# easy_bee_feather_route.net
KiCad netlist of a schematic drawn in EAGLE
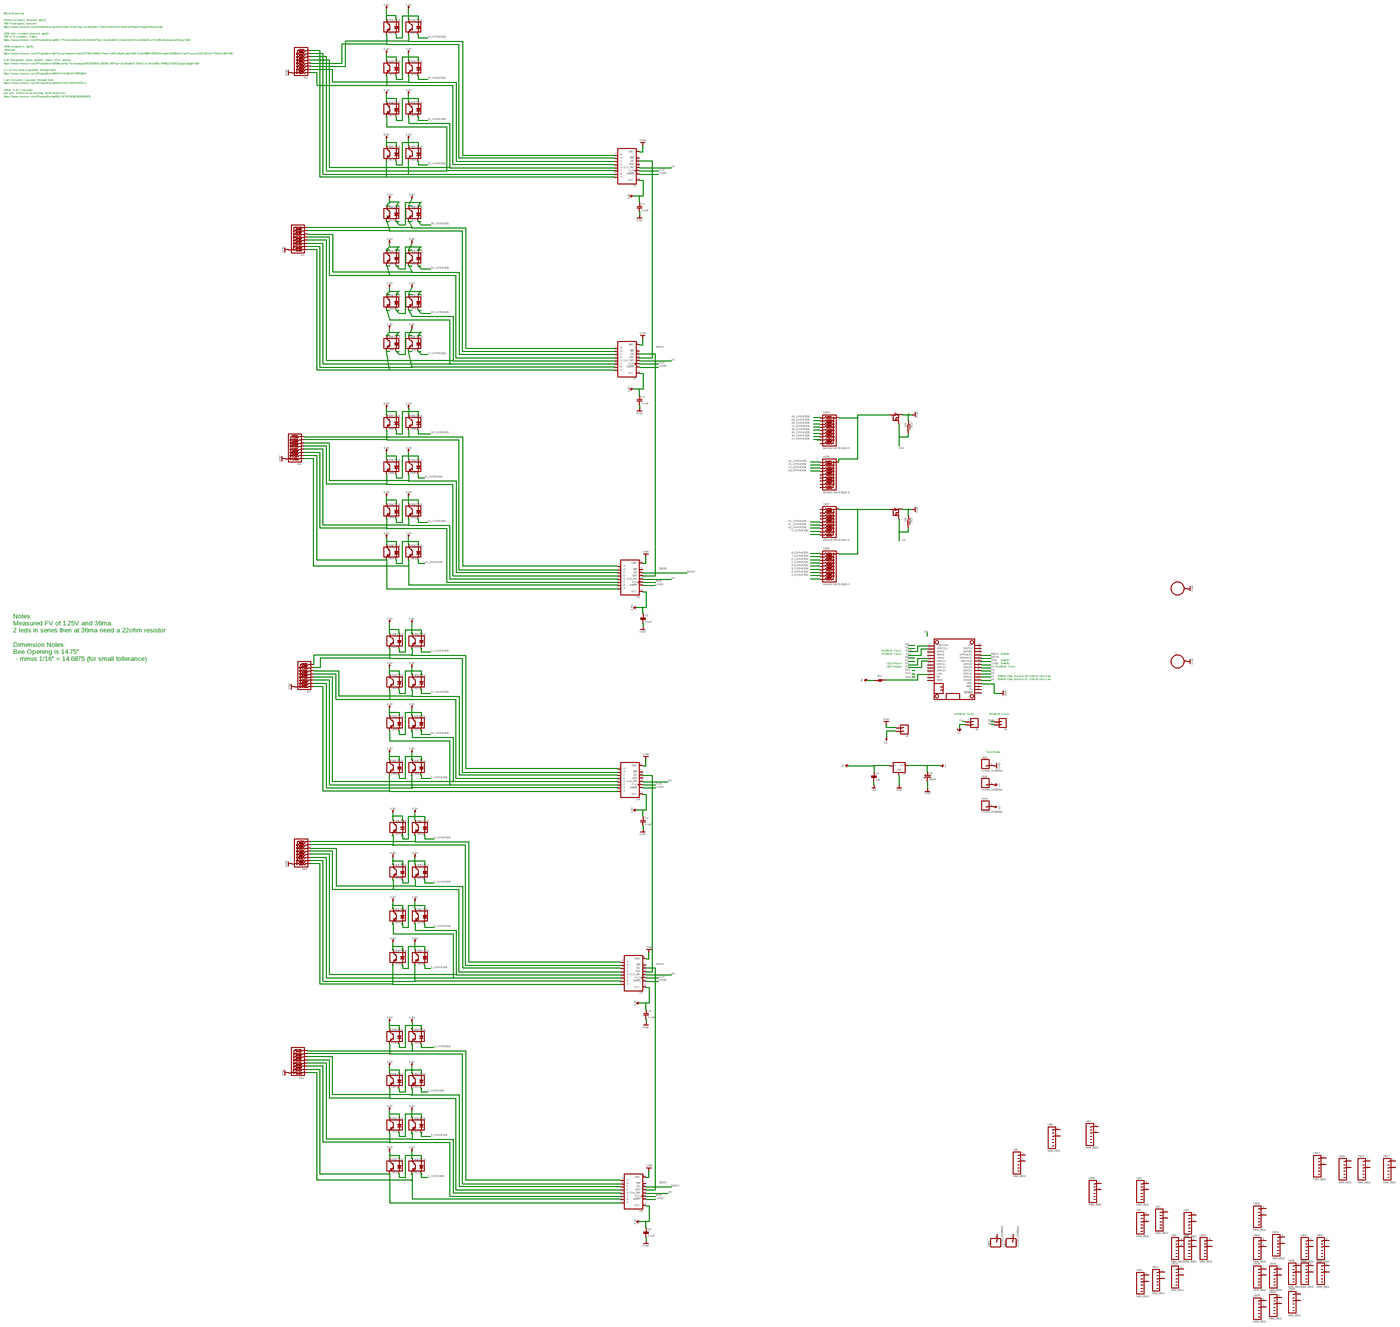
[diagram p0: schematic, sheet 1, overview]
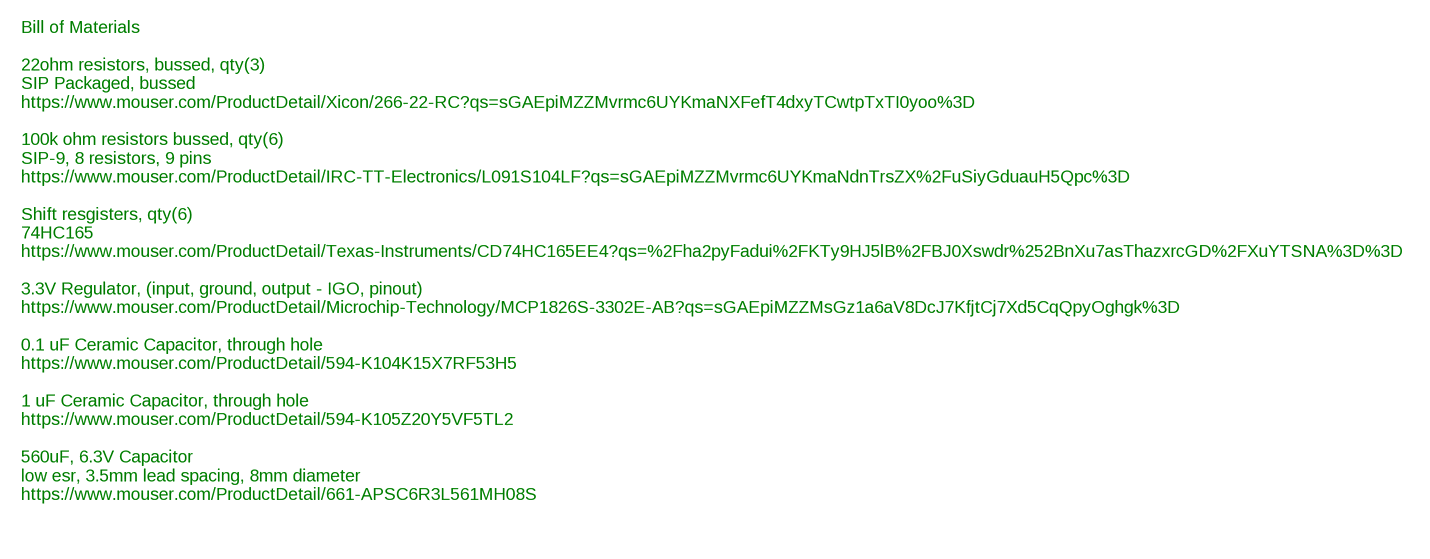
[diagram p1: schematic, sheet 1, part 1 of 5]
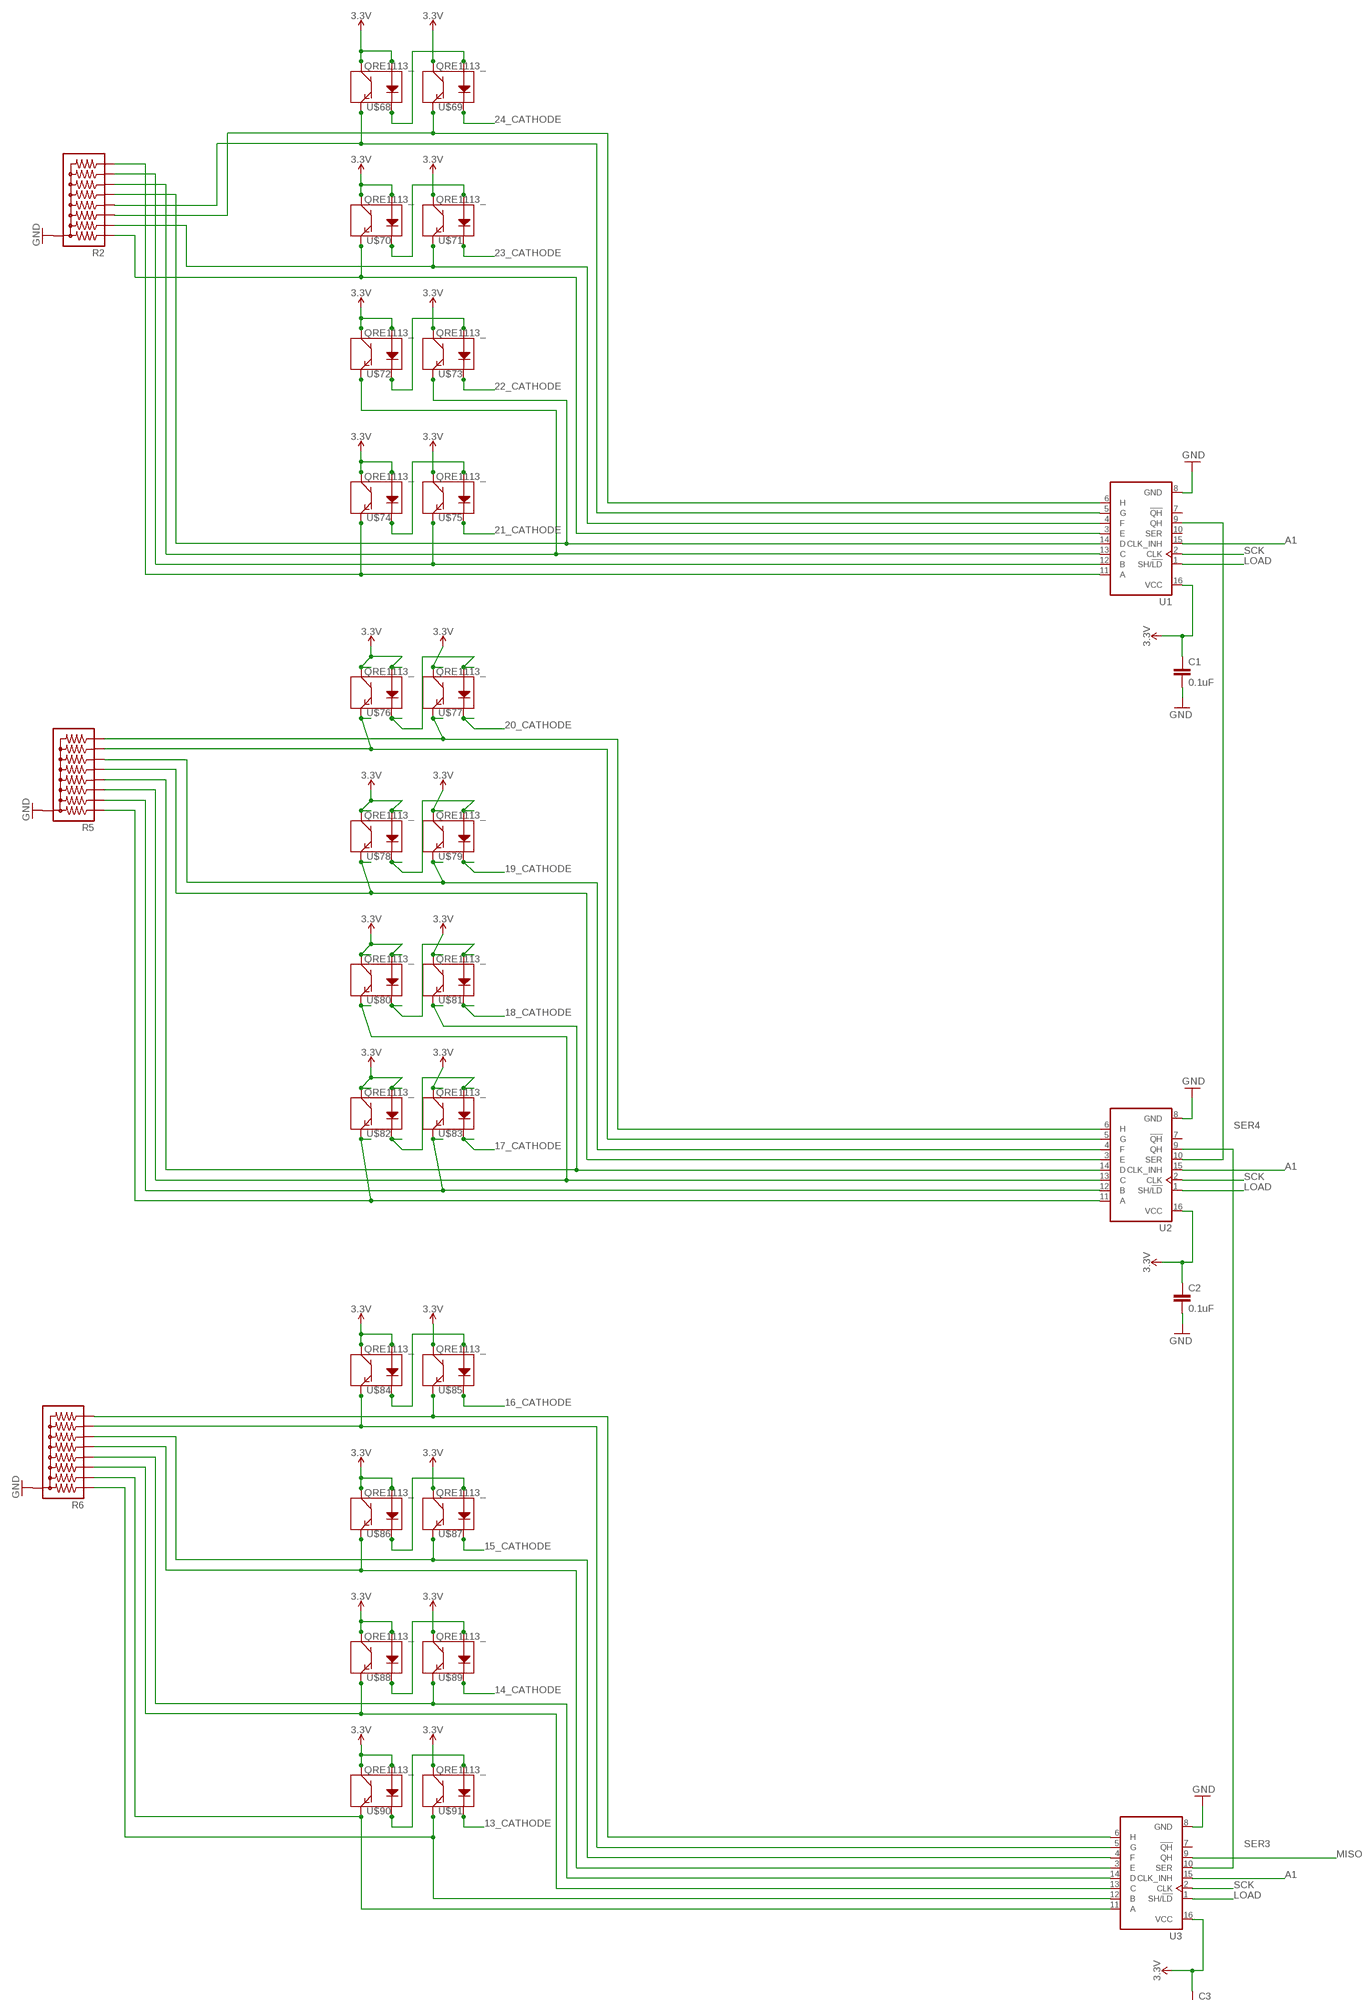
[diagram p2: schematic, sheet 1, part 2 of 5]
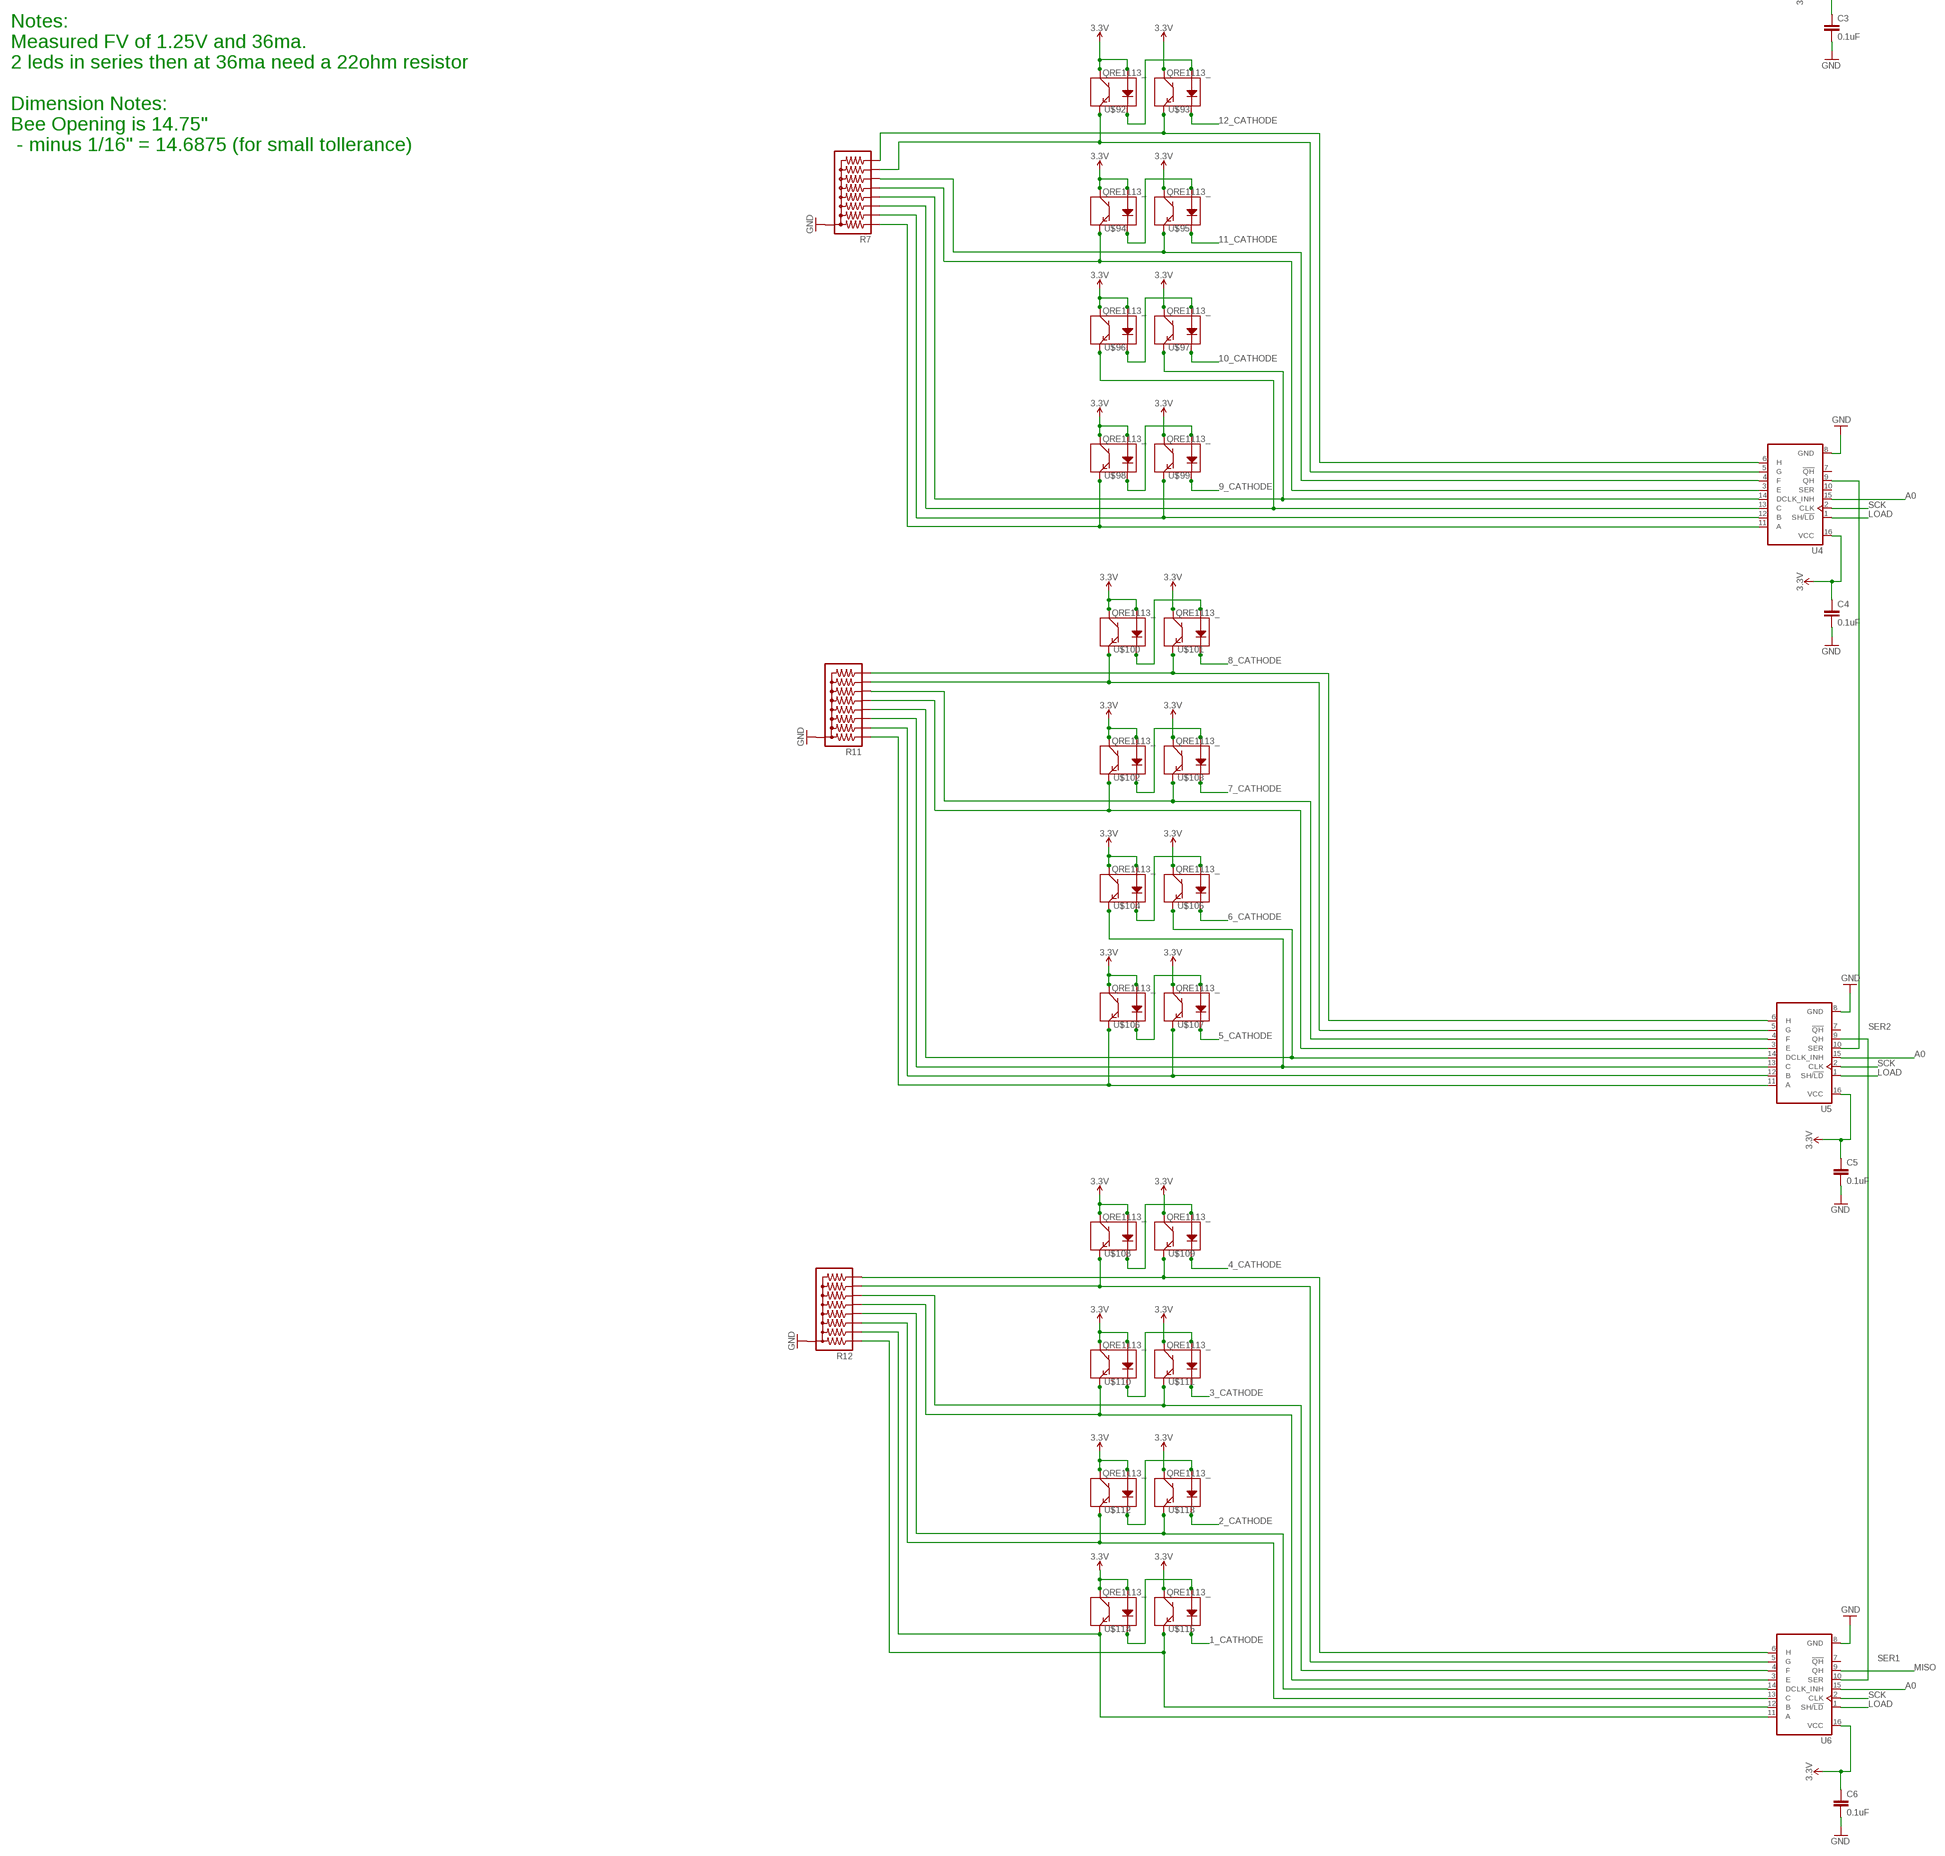
[diagram p3: schematic, sheet 1, part 3 of 5]
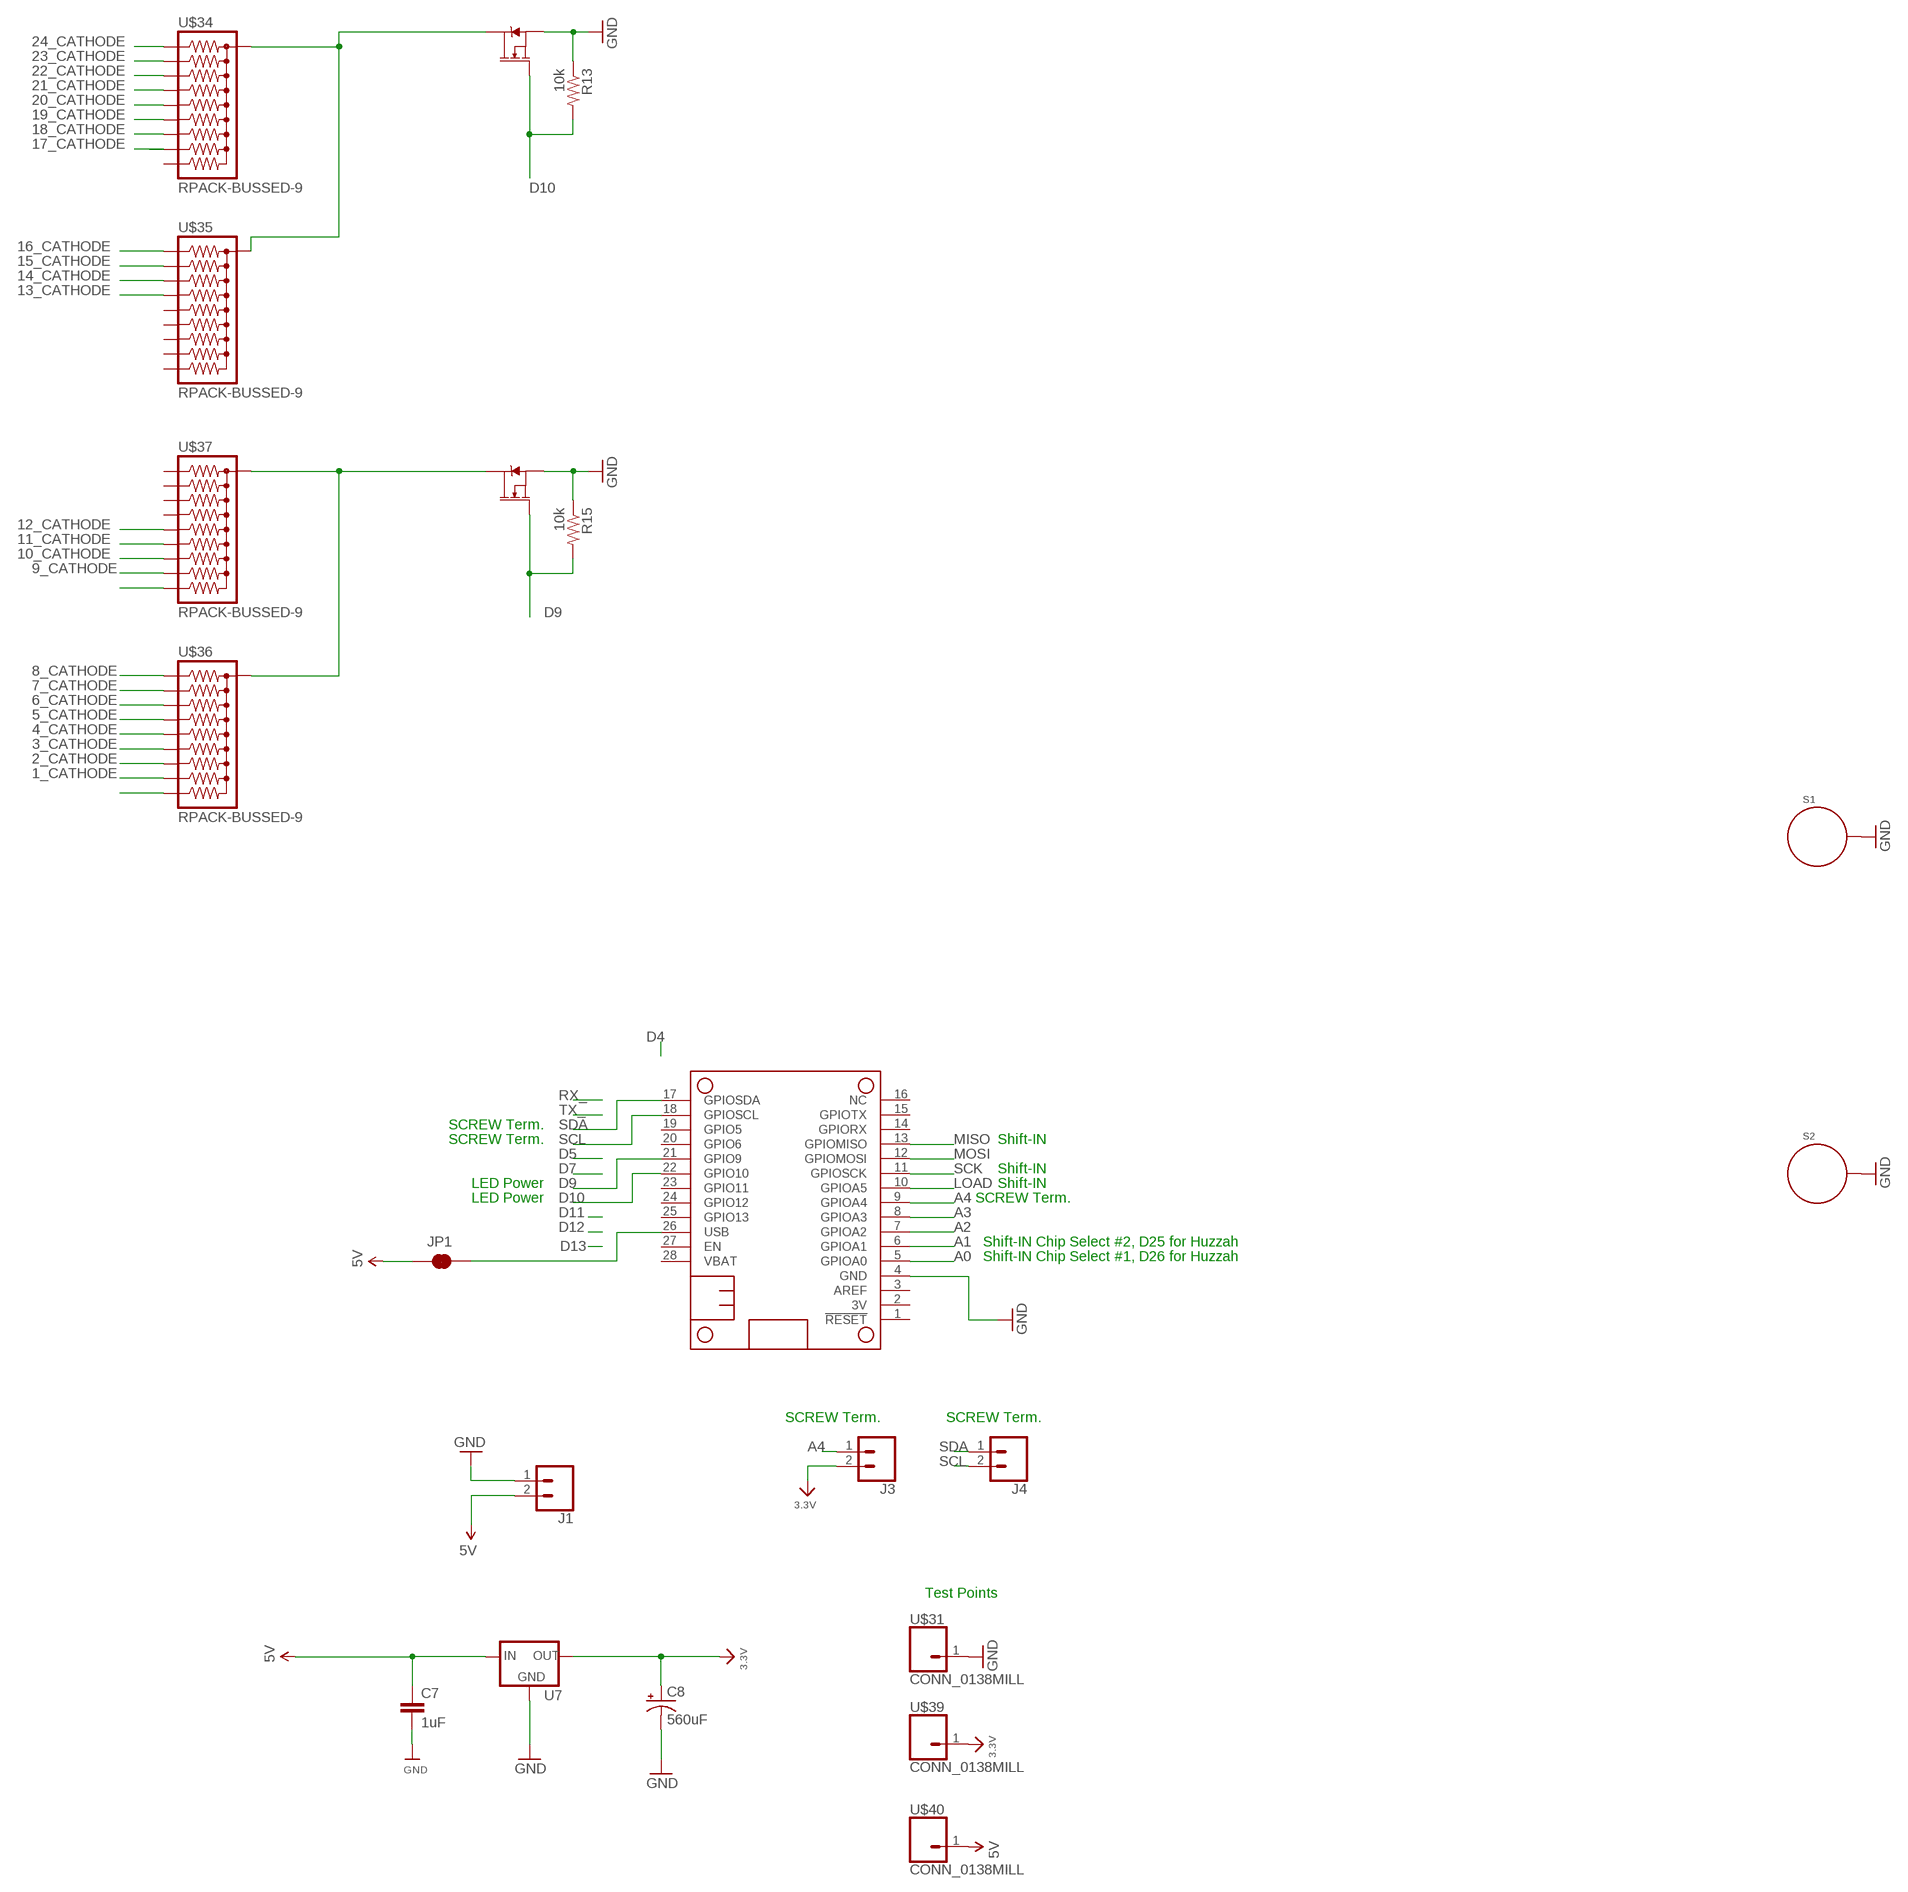
[diagram p4: schematic, sheet 1, part 4 of 5]
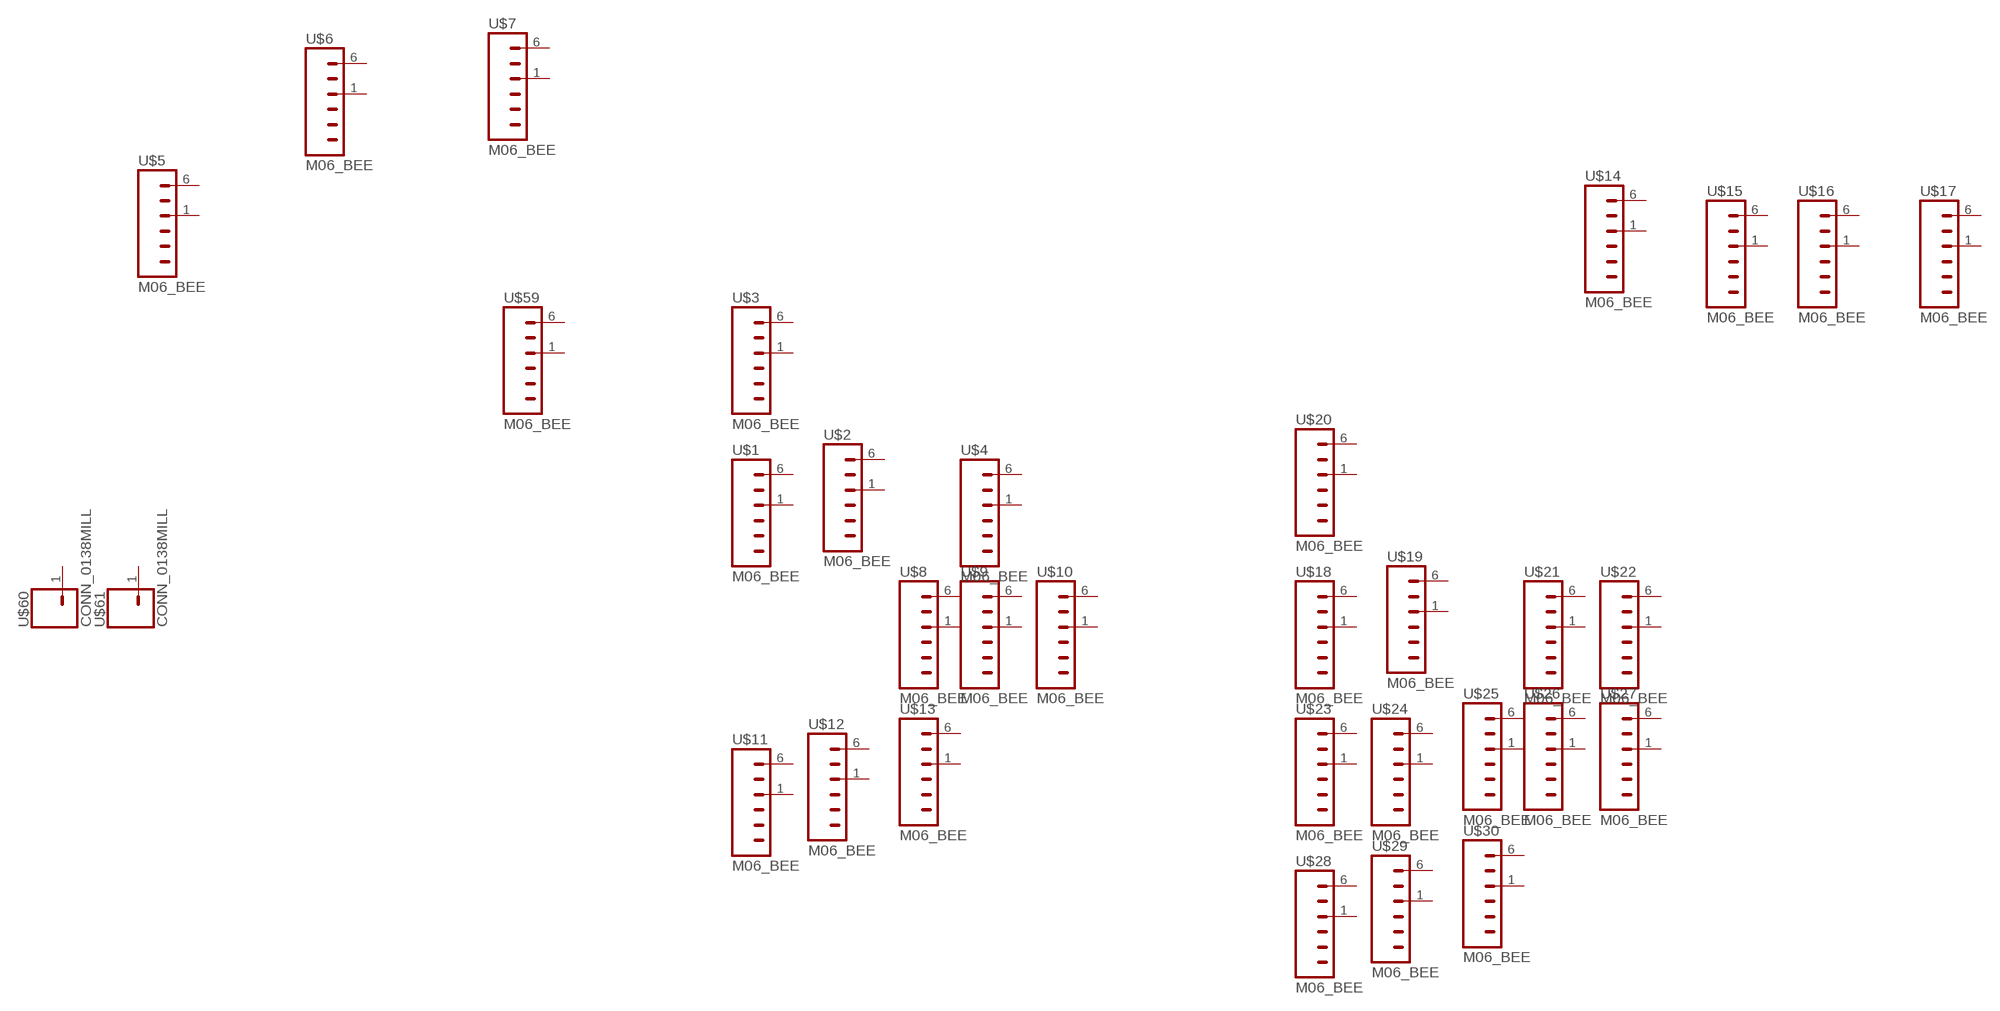
[diagram p5: schematic, sheet 1, part 5 of 5]

(export (version "E")
  (design (tool "Eeschema 10.0.6"))
  (components
    (comp (ref "C1")
      (value "0.1uF")
      (footprint "eagle-import:CAP-PTH-SMALL-KIT")
      (libsource (lib "eagle-import") (part "0.1UF-KIT-EZ-50V-20%"))
    )
    (comp (ref "C2")
      (value "0.1uF")
      (footprint "eagle-import:CAP-PTH-SMALL-KIT")
      (libsource (lib "eagle-import") (part "0.1UF-KIT-EZ-50V-20%"))
    )
    (comp (ref "C3")
      (value "0.1uF")
      (footprint "eagle-import:CAP-PTH-SMALL-KIT")
      (libsource (lib "eagle-import") (part "0.1UF-KIT-EZ-50V-20%"))
    )
    (comp (ref "C4")
      (value "0.1uF")
      (footprint "eagle-import:CAP-PTH-SMALL-KIT")
      (libsource (lib "eagle-import") (part "0.1UF-KIT-EZ-50V-20%"))
    )
    (comp (ref "C5")
      (value "0.1uF")
      (footprint "eagle-import:CAP-PTH-SMALL-KIT")
      (libsource (lib "eagle-import") (part "0.1UF-KIT-EZ-50V-20%"))
    )
    (comp (ref "C6")
      (value "0.1uF")
      (footprint "eagle-import:CAP-PTH-SMALL-KIT")
      (libsource (lib "eagle-import") (part "0.1UF-KIT-EZ-50V-20%"))
    )
    (comp (ref "C7")
      (value "1uF")
      (footprint "eagle-import:CAP-PTH-SMALL-KIT")
      (libsource (lib "eagle-import") (part "0.1UF-KIT-EZ-50V-20%"))
    )
    (comp (ref "C8")
      (value "560uF")
      (footprint "eagle-import:E3,5-8")
      (libsource (lib "eagle-import") (part "CPOL-USE3.5-8"))
    )
    (comp (ref "J1")
      (value "CONN_025MM")
      (footprint "eagle-import:SCREWTERMINAL-5MM-2")
      (libsource (lib "eagle-import") (part "CONN_025MM"))
    )
    (comp (ref "J3")
      (value "CONN_025MM")
      (footprint "eagle-import:SCREWTERMINAL-5MM-2")
      (libsource (lib "eagle-import") (part "CONN_025MM"))
    )
    (comp (ref "J4")
      (value "CONN_025MM")
      (footprint "eagle-import:SCREWTERMINAL-5MM-2")
      (libsource (lib "eagle-import") (part "CONN_025MM"))
    )
    (comp (ref "JP1")
      (value "JUMPER-SMT_2_NC_TRACE_SILK")
      (footprint "eagle-import:SMT-JUMPER_2_NC_TRACE_SILK")
      (libsource (lib "eagle-import") (part "JUMPER-SMT_2_NC_TRACE_SILK"))
    )
    (comp (ref "MS2")
      (value "FEATHERWING_NODIM")
      (footprint "eagle-import:FEATHERWING_DIM")
      (libsource (lib "eagle-import") (part "FEATHERWING_NODIM"))
    )
    (comp (ref "Q6")
      (value "60V/32A/35mΩ")
      (footprint "eagle-import:TO220V")
      (libsource (lib "eagle-import") (part "MOSFET-NCH-FQP30N06L"))
    )
    (comp (ref "Q7")
      (value "60V/32A/35mΩ")
      (footprint "eagle-import:TO220V")
      (libsource (lib "eagle-import") (part "MOSFET-NCH-FQP30N06L"))
    )
    (comp (ref "R2")
      (value "RPACK-BUSSED-8-SIP-PTH-8")
      (footprint "eagle-import:RPACK-SIP-PTH-8")
      (libsource (lib "eagle-import") (part "RPACK-BUSSED-8-SIP-PTH-8"))
    )
    (comp (ref "R5")
      (value "RPACK-BUSSED-8-SIP-PTH-8")
      (footprint "eagle-import:RPACK-SIP-PTH-8")
      (libsource (lib "eagle-import") (part "RPACK-BUSSED-8-SIP-PTH-8"))
    )
    (comp (ref "R6")
      (value "RPACK-BUSSED-8-SIP-PTH-8")
      (footprint "eagle-import:RPACK-SIP-PTH-8")
      (libsource (lib "eagle-import") (part "RPACK-BUSSED-8-SIP-PTH-8"))
    )
    (comp (ref "R7")
      (value "RPACK-BUSSED-8-SIP-PTH-8")
      (footprint "eagle-import:RPACK-SIP-PTH-8")
      (libsource (lib "eagle-import") (part "RPACK-BUSSED-8-SIP-PTH-8"))
    )
    (comp (ref "R11")
      (value "RPACK-BUSSED-8-SIP-PTH-8")
      (footprint "eagle-import:RPACK-SIP-PTH-8")
      (libsource (lib "eagle-import") (part "RPACK-BUSSED-8-SIP-PTH-8"))
    )
    (comp (ref "R12")
      (value "RPACK-BUSSED-8-SIP-PTH-8")
      (footprint "eagle-import:RPACK-SIP-PTH-8")
      (libsource (lib "eagle-import") (part "RPACK-BUSSED-8-SIP-PTH-8"))
    )
    (comp (ref "R13")
      (value "10k")
      (footprint "eagle-import:AXIAL-0.3")
      (libsource (lib "eagle-import") (part "RESISTORAXIAL-0.3"))
    )
    (comp (ref "R15")
      (value "10k")
      (footprint "eagle-import:AXIAL-0.3")
      (libsource (lib "eagle-import") (part "RESISTORAXIAL-0.3"))
    )
    (comp (ref "S1")
      (value "STANDOFF_ELECTRICAL5-32")
      (footprint "eagle-import:STANDOFF_ELECTRICAL_5_32")
      (libsource (lib "eagle-import") (part "STANDOFF_ELECTRICAL5-32"))
    )
    (comp (ref "S2")
      (value "STANDOFF_ELECTRICAL5-32")
      (footprint "eagle-import:STANDOFF_ELECTRICAL_5_32")
      (libsource (lib "eagle-import") (part "STANDOFF_ELECTRICAL5-32"))
    )
    (comp (ref "U$1")
      (value "M06_BEE")
      (footprint "eagle-import:1X06_BEE")
      (libsource (lib "eagle-import") (part "M06_BEE"))
    )
    (comp (ref "U$2")
      (value "M06_BEE")
      (footprint "eagle-import:1X06_BEE")
      (libsource (lib "eagle-import") (part "M06_BEE"))
    )
    (comp (ref "U$3")
      (value "M06_BEE")
      (footprint "eagle-import:1X06_BEE")
      (libsource (lib "eagle-import") (part "M06_BEE"))
    )
    (comp (ref "U$4")
      (value "M06_BEE")
      (footprint "eagle-import:1X06_BEE")
      (libsource (lib "eagle-import") (part "M06_BEE"))
    )
    (comp (ref "U$5")
      (value "M06_BEE")
      (footprint "eagle-import:1X06_BEE")
      (libsource (lib "eagle-import") (part "M06_BEE"))
    )
    (comp (ref "U$6")
      (value "M06_BEE")
      (footprint "eagle-import:1X06_BEE")
      (libsource (lib "eagle-import") (part "M06_BEE"))
    )
    (comp (ref "U$7")
      (value "M06_BEE")
      (footprint "eagle-import:1X06_BEE")
      (libsource (lib "eagle-import") (part "M06_BEE"))
    )
    (comp (ref "U$8")
      (value "M06_BEE")
      (footprint "eagle-import:1X06_BEE")
      (libsource (lib "eagle-import") (part "M06_BEE"))
    )
    (comp (ref "U$9")
      (value "M06_BEE")
      (footprint "eagle-import:1X06_BEE")
      (libsource (lib "eagle-import") (part "M06_BEE"))
    )
    (comp (ref "U$10")
      (value "M06_BEE")
      (footprint "eagle-import:1X06_BEE")
      (libsource (lib "eagle-import") (part "M06_BEE"))
    )
    (comp (ref "U$11")
      (value "M06_BEE")
      (footprint "eagle-import:1X06_BEE")
      (libsource (lib "eagle-import") (part "M06_BEE"))
    )
    (comp (ref "U$12")
      (value "M06_BEE")
      (footprint "eagle-import:1X06_BEE")
      (libsource (lib "eagle-import") (part "M06_BEE"))
    )
    (comp (ref "U$13")
      (value "M06_BEE")
      (footprint "eagle-import:1X06_BEE")
      (libsource (lib "eagle-import") (part "M06_BEE"))
    )
    (comp (ref "U$14")
      (value "M06_BEE")
      (footprint "eagle-import:1X06_BEE")
      (libsource (lib "eagle-import") (part "M06_BEE"))
    )
    (comp (ref "U$15")
      (value "M06_BEE")
      (footprint "eagle-import:1X06_BEE")
      (libsource (lib "eagle-import") (part "M06_BEE"))
    )
    (comp (ref "U$16")
      (value "M06_BEE")
      (footprint "eagle-import:1X06_BEE")
      (libsource (lib "eagle-import") (part "M06_BEE"))
    )
    (comp (ref "U$17")
      (value "M06_BEE")
      (footprint "eagle-import:1X06_BEE")
      (libsource (lib "eagle-import") (part "M06_BEE"))
    )
    (comp (ref "U$18")
      (value "M06_BEE")
      (footprint "eagle-import:1X06_BEE")
      (libsource (lib "eagle-import") (part "M06_BEE"))
    )
    (comp (ref "U$19")
      (value "M06_BEE")
      (footprint "eagle-import:1X06_BEE")
      (libsource (lib "eagle-import") (part "M06_BEE"))
    )
    (comp (ref "U$20")
      (value "M06_BEE")
      (footprint "eagle-import:1X06_BEE")
      (libsource (lib "eagle-import") (part "M06_BEE"))
    )
    (comp (ref "U$21")
      (value "M06_BEE")
      (footprint "eagle-import:1X06_BEE")
      (libsource (lib "eagle-import") (part "M06_BEE"))
    )
    (comp (ref "U$22")
      (value "M06_BEE")
      (footprint "eagle-import:1X06_BEE")
      (libsource (lib "eagle-import") (part "M06_BEE"))
    )
    (comp (ref "U$23")
      (value "M06_BEE")
      (footprint "eagle-import:1X06_BEE")
      (libsource (lib "eagle-import") (part "M06_BEE"))
    )
    (comp (ref "U$24")
      (value "M06_BEE")
      (footprint "eagle-import:1X06_BEE")
      (libsource (lib "eagle-import") (part "M06_BEE"))
    )
    (comp (ref "U$25")
      (value "M06_BEE")
      (footprint "eagle-import:1X06_BEE")
      (libsource (lib "eagle-import") (part "M06_BEE"))
    )
    (comp (ref "U$26")
      (value "M06_BEE")
      (footprint "eagle-import:1X06_BEE")
      (libsource (lib "eagle-import") (part "M06_BEE"))
    )
    (comp (ref "U$27")
      (value "M06_BEE")
      (footprint "eagle-import:1X06_BEE")
      (libsource (lib "eagle-import") (part "M06_BEE"))
    )
    (comp (ref "U$28")
      (value "M06_BEE")
      (footprint "eagle-import:1X06_BEE")
      (libsource (lib "eagle-import") (part "M06_BEE"))
    )
    (comp (ref "U$29")
      (value "M06_BEE")
      (footprint "eagle-import:1X06_BEE")
      (libsource (lib "eagle-import") (part "M06_BEE"))
    )
    (comp (ref "U$30")
      (value "M06_BEE")
      (footprint "eagle-import:1X06_BEE")
      (libsource (lib "eagle-import") (part "M06_BEE"))
    )
    (comp (ref "U$31")
      (value "CONN_0138MILL")
      (footprint "eagle-import:1X01-40MILL")
      (libsource (lib "eagle-import") (part "CONN_0138MILL"))
    )
    (comp (ref "U$34")
      (value "RPACK-BUSSED-9")
      (footprint "eagle-import:RPACK-SIP-PTH-9")
      (libsource (lib "eagle-import") (part "RPACK-BUSSED-9"))
    )
    (comp (ref "U$35")
      (value "RPACK-BUSSED-9")
      (footprint "eagle-import:RPACK-SIP-PTH-9")
      (libsource (lib "eagle-import") (part "RPACK-BUSSED-9"))
    )
    (comp (ref "U$36")
      (value "RPACK-BUSSED-9")
      (footprint "eagle-import:RPACK-SIP-PTH-9")
      (libsource (lib "eagle-import") (part "RPACK-BUSSED-9"))
    )
    (comp (ref "U$37")
      (value "RPACK-BUSSED-9")
      (footprint "eagle-import:RPACK-SIP-PTH-9")
      (libsource (lib "eagle-import") (part "RPACK-BUSSED-9"))
    )
    (comp (ref "U$39")
      (value "CONN_0138MILL")
      (footprint "eagle-import:1X01-40MILL")
      (libsource (lib "eagle-import") (part "CONN_0138MILL"))
    )
    (comp (ref "U$40")
      (value "CONN_0138MILL")
      (footprint "eagle-import:1X01-40MILL")
      (libsource (lib "eagle-import") (part "CONN_0138MILL"))
    )
    (comp (ref "U$59")
      (value "M06_BEE")
      (footprint "eagle-import:1X06_BEE")
      (libsource (lib "eagle-import") (part "M06_BEE"))
    )
    (comp (ref "U$60")
      (value "CONN_0138MILL")
      (footprint "eagle-import:1X01-40MILL")
      (libsource (lib "eagle-import") (part "CONN_0138MILL"))
    )
    (comp (ref "U$61")
      (value "CONN_0138MILL")
      (footprint "eagle-import:1X01-40MILL")
      (libsource (lib "eagle-import") (part "CONN_0138MILL"))
    )
    (comp (ref "U$68")
      (value "QRE1113_")
      (footprint "eagle-import:DIP400W50P180L360H200Q4")
      (libsource (lib "eagle-import") (part "QRE1113_"))
    )
    (comp (ref "U$69")
      (value "QRE1113_")
      (footprint "eagle-import:DIP400W50P180L360H200Q4")
      (libsource (lib "eagle-import") (part "QRE1113_"))
    )
    (comp (ref "U$70")
      (value "QRE1113_")
      (footprint "eagle-import:DIP400W50P180L360H200Q4")
      (libsource (lib "eagle-import") (part "QRE1113_"))
    )
    (comp (ref "U$71")
      (value "QRE1113_")
      (footprint "eagle-import:DIP400W50P180L360H200Q4")
      (libsource (lib "eagle-import") (part "QRE1113_"))
    )
    (comp (ref "U$72")
      (value "QRE1113_")
      (footprint "eagle-import:DIP400W50P180L360H200Q4")
      (libsource (lib "eagle-import") (part "QRE1113_"))
    )
    (comp (ref "U$73")
      (value "QRE1113_")
      (footprint "eagle-import:DIP400W50P180L360H200Q4")
      (libsource (lib "eagle-import") (part "QRE1113_"))
    )
    (comp (ref "U$74")
      (value "QRE1113_")
      (footprint "eagle-import:DIP400W50P180L360H200Q4")
      (libsource (lib "eagle-import") (part "QRE1113_"))
    )
    (comp (ref "U$75")
      (value "QRE1113_")
      (footprint "eagle-import:DIP400W50P180L360H200Q4")
      (libsource (lib "eagle-import") (part "QRE1113_"))
    )
    (comp (ref "U$76")
      (value "QRE1113_")
      (footprint "eagle-import:DIP400W50P180L360H200Q4")
      (libsource (lib "eagle-import") (part "QRE1113_"))
    )
    (comp (ref "U$77")
      (value "QRE1113_")
      (footprint "eagle-import:DIP400W50P180L360H200Q4")
      (libsource (lib "eagle-import") (part "QRE1113_"))
    )
    (comp (ref "U$78")
      (value "QRE1113_")
      (footprint "eagle-import:DIP400W50P180L360H200Q4")
      (libsource (lib "eagle-import") (part "QRE1113_"))
    )
    (comp (ref "U$79")
      (value "QRE1113_")
      (footprint "eagle-import:DIP400W50P180L360H200Q4")
      (libsource (lib "eagle-import") (part "QRE1113_"))
    )
    (comp (ref "U$80")
      (value "QRE1113_")
      (footprint "eagle-import:DIP400W50P180L360H200Q4")
      (libsource (lib "eagle-import") (part "QRE1113_"))
    )
    (comp (ref "U$81")
      (value "QRE1113_")
      (footprint "eagle-import:DIP400W50P180L360H200Q4")
      (libsource (lib "eagle-import") (part "QRE1113_"))
    )
    (comp (ref "U$82")
      (value "QRE1113_")
      (footprint "eagle-import:DIP400W50P180L360H200Q4")
      (libsource (lib "eagle-import") (part "QRE1113_"))
    )
    (comp (ref "U$83")
      (value "QRE1113_")
      (footprint "eagle-import:DIP400W50P180L360H200Q4")
      (libsource (lib "eagle-import") (part "QRE1113_"))
    )
    (comp (ref "U$84")
      (value "QRE1113_")
      (footprint "eagle-import:DIP400W50P180L360H200Q4")
      (libsource (lib "eagle-import") (part "QRE1113_"))
    )
    (comp (ref "U$85")
      (value "QRE1113_")
      (footprint "eagle-import:DIP400W50P180L360H200Q4")
      (libsource (lib "eagle-import") (part "QRE1113_"))
    )
    (comp (ref "U$86")
      (value "QRE1113_")
      (footprint "eagle-import:DIP400W50P180L360H200Q4")
      (libsource (lib "eagle-import") (part "QRE1113_"))
    )
    (comp (ref "U$87")
      (value "QRE1113_")
      (footprint "eagle-import:DIP400W50P180L360H200Q4")
      (libsource (lib "eagle-import") (part "QRE1113_"))
    )
    (comp (ref "U$88")
      (value "QRE1113_")
      (footprint "eagle-import:DIP400W50P180L360H200Q4")
      (libsource (lib "eagle-import") (part "QRE1113_"))
    )
    (comp (ref "U$89")
      (value "QRE1113_")
      (footprint "eagle-import:DIP400W50P180L360H200Q4")
      (libsource (lib "eagle-import") (part "QRE1113_"))
    )
    (comp (ref "U$90")
      (value "QRE1113_")
      (footprint "eagle-import:DIP400W50P180L360H200Q4")
      (libsource (lib "eagle-import") (part "QRE1113_"))
    )
    (comp (ref "U$91")
      (value "QRE1113_")
      (footprint "eagle-import:DIP400W50P180L360H200Q4")
      (libsource (lib "eagle-import") (part "QRE1113_"))
    )
    (comp (ref "U$92")
      (value "QRE1113_")
      (footprint "eagle-import:DIP400W50P180L360H200Q4")
      (libsource (lib "eagle-import") (part "QRE1113_"))
    )
    (comp (ref "U$93")
      (value "QRE1113_")
      (footprint "eagle-import:DIP400W50P180L360H200Q4")
      (libsource (lib "eagle-import") (part "QRE1113_"))
    )
    (comp (ref "U$94")
      (value "QRE1113_")
      (footprint "eagle-import:DIP400W50P180L360H200Q4")
      (libsource (lib "eagle-import") (part "QRE1113_"))
    )
    (comp (ref "U$95")
      (value "QRE1113_")
      (footprint "eagle-import:DIP400W50P180L360H200Q4")
      (libsource (lib "eagle-import") (part "QRE1113_"))
    )
    (comp (ref "U$96")
      (value "QRE1113_")
      (footprint "eagle-import:DIP400W50P180L360H200Q4")
      (libsource (lib "eagle-import") (part "QRE1113_"))
    )
    (comp (ref "U$97")
      (value "QRE1113_")
      (footprint "eagle-import:DIP400W50P180L360H200Q4")
      (libsource (lib "eagle-import") (part "QRE1113_"))
    )
    (comp (ref "U$98")
      (value "QRE1113_")
      (footprint "eagle-import:DIP400W50P180L360H200Q4")
      (libsource (lib "eagle-import") (part "QRE1113_"))
    )
    (comp (ref "U$99")
      (value "QRE1113_")
      (footprint "eagle-import:DIP400W50P180L360H200Q4")
      (libsource (lib "eagle-import") (part "QRE1113_"))
    )
    (comp (ref "U$100")
      (value "QRE1113_")
      (footprint "eagle-import:DIP400W50P180L360H200Q4")
      (libsource (lib "eagle-import") (part "QRE1113_"))
    )
    (comp (ref "U$101")
      (value "QRE1113_")
      (footprint "eagle-import:DIP400W50P180L360H200Q4")
      (libsource (lib "eagle-import") (part "QRE1113_"))
    )
    (comp (ref "U$102")
      (value "QRE1113_")
      (footprint "eagle-import:DIP400W50P180L360H200Q4")
      (libsource (lib "eagle-import") (part "QRE1113_"))
    )
    (comp (ref "U$103")
      (value "QRE1113_")
      (footprint "eagle-import:DIP400W50P180L360H200Q4")
      (libsource (lib "eagle-import") (part "QRE1113_"))
    )
    (comp (ref "U$104")
      (value "QRE1113_")
      (footprint "eagle-import:DIP400W50P180L360H200Q4")
      (libsource (lib "eagle-import") (part "QRE1113_"))
    )
    (comp (ref "U$105")
      (value "QRE1113_")
      (footprint "eagle-import:DIP400W50P180L360H200Q4")
      (libsource (lib "eagle-import") (part "QRE1113_"))
    )
    (comp (ref "U$106")
      (value "QRE1113_")
      (footprint "eagle-import:DIP400W50P180L360H200Q4")
      (libsource (lib "eagle-import") (part "QRE1113_"))
    )
    (comp (ref "U$107")
      (value "QRE1113_")
      (footprint "eagle-import:DIP400W50P180L360H200Q4")
      (libsource (lib "eagle-import") (part "QRE1113_"))
    )
    (comp (ref "U$108")
      (value "QRE1113_")
      (footprint "eagle-import:DIP400W50P180L360H200Q4")
      (libsource (lib "eagle-import") (part "QRE1113_"))
    )
    (comp (ref "U$109")
      (value "QRE1113_")
      (footprint "eagle-import:DIP400W50P180L360H200Q4")
      (libsource (lib "eagle-import") (part "QRE1113_"))
    )
    (comp (ref "U$110")
      (value "QRE1113_")
      (footprint "eagle-import:DIP400W50P180L360H200Q4")
      (libsource (lib "eagle-import") (part "QRE1113_"))
    )
    (comp (ref "U$111")
      (value "QRE1113_")
      (footprint "eagle-import:DIP400W50P180L360H200Q4")
      (libsource (lib "eagle-import") (part "QRE1113_"))
    )
    (comp (ref "U$112")
      (value "QRE1113_")
      (footprint "eagle-import:DIP400W50P180L360H200Q4")
      (libsource (lib "eagle-import") (part "QRE1113_"))
    )
    (comp (ref "U$113")
      (value "QRE1113_")
      (footprint "eagle-import:DIP400W50P180L360H200Q4")
      (libsource (lib "eagle-import") (part "QRE1113_"))
    )
    (comp (ref "U$114")
      (value "QRE1113_")
      (footprint "eagle-import:DIP400W50P180L360H200Q4")
      (libsource (lib "eagle-import") (part "QRE1113_"))
    )
    (comp (ref "U$115")
      (value "QRE1113_")
      (footprint "eagle-import:DIP400W50P180L360H200Q4")
      (libsource (lib "eagle-import") (part "QRE1113_"))
    )
    (comp (ref "U1")
      (value "74165")
      (footprint "eagle-import:DIP16")
      (libsource (lib "eagle-import") (part "74165"))
    )
    (comp (ref "U2")
      (value "74165")
      (footprint "eagle-import:DIP16")
      (libsource (lib "eagle-import") (part "74165"))
    )
    (comp (ref "U3")
      (value "74165")
      (footprint "eagle-import:DIP16")
      (libsource (lib "eagle-import") (part "74165"))
    )
    (comp (ref "U4")
      (value "74165")
      (footprint "eagle-import:DIP16")
      (libsource (lib "eagle-import") (part "74165"))
    )
    (comp (ref "U5")
      (value "74165")
      (footprint "eagle-import:DIP16")
      (libsource (lib "eagle-import") (part "74165"))
    )
    (comp (ref "U6")
      (value "74165")
      (footprint "eagle-import:DIP16")
      (libsource (lib "eagle-import") (part "74165"))
    )
    (comp (ref "U7")
      (value "V_REG_78XXSINK")
      (footprint "eagle-import:TO220-IGO")
      (libsource (lib "eagle-import") (part "V_REG_78XXSINK"))
    )
  )
  (nets
    (net (code "1") (name "/1_CATHODE") (class "Default")
      (node (ref "U$115") (pin "2") (pinfunction "K_2") (pintype "bidirectional"))
      (node (ref "U$36") (pin "P$9") (pinfunction "9_P$9") (pintype "passive"))
    )
    (net (code "2") (name "/2_CATHODE") (class "Default")
      (node (ref "U$113") (pin "2") (pinfunction "K_2") (pintype "bidirectional"))
      (node (ref "U$36") (pin "P$8") (pinfunction "8_P$8") (pintype "passive"))
    )
    (net (code "3") (name "/3V") (class "Default")
      (node (ref "MS2") (pin "2") (pinfunction "3V_2") (pintype "power_in"))
    )
    (net (code "4") (name "/3_CATHODE") (class "Default")
      (node (ref "U$111") (pin "2") (pinfunction "K_2") (pintype "bidirectional"))
      (node (ref "U$36") (pin "P$7") (pinfunction "7_P$7") (pintype "passive"))
    )
    (net (code "5") (name "/4_CATHODE") (class "Default")
      (node (ref "U$109") (pin "2") (pinfunction "K_2") (pintype "bidirectional"))
      (node (ref "U$36") (pin "P$6") (pinfunction "6_P$6") (pintype "passive"))
    )
    (net (code "6") (name "/5_CATHODE") (class "Default")
      (node (ref "U$107") (pin "2") (pinfunction "K_2") (pintype "bidirectional"))
      (node (ref "U$36") (pin "P$5") (pinfunction "5_P$5") (pintype "passive"))
    )
    (net (code "7") (name "/6_CATHODE") (class "Default")
      (node (ref "U$105") (pin "2") (pinfunction "K_2") (pintype "bidirectional"))
      (node (ref "U$36") (pin "P$4") (pinfunction "4_P$4") (pintype "passive"))
    )
    (net (code "8") (name "/7_CATHODE") (class "Default")
      (node (ref "U$103") (pin "2") (pinfunction "K_2") (pintype "bidirectional"))
      (node (ref "U$36") (pin "P$3") (pinfunction "3_P$3") (pintype "passive"))
    )
    (net (code "9") (name "/8_CATHODE") (class "Default")
      (node (ref "U$101") (pin "2") (pinfunction "K_2") (pintype "bidirectional"))
      (node (ref "U$36") (pin "P$2") (pinfunction "2_P$2") (pintype "passive"))
    )
    (net (code "10") (name "/9_CATHODE") (class "Default")
      (node (ref "U$37") (pin "P$9") (pinfunction "9_P$9") (pintype "passive"))
      (node (ref "U$99") (pin "2") (pinfunction "K_2") (pintype "bidirectional"))
    )
    (net (code "11") (name "/10_CATHODE") (class "Default")
      (node (ref "U$37") (pin "P$8") (pinfunction "8_P$8") (pintype "passive"))
      (node (ref "U$97") (pin "2") (pinfunction "K_2") (pintype "bidirectional"))
    )
    (net (code "12") (name "/11_CATHODE") (class "Default")
      (node (ref "U$37") (pin "P$7") (pinfunction "7_P$7") (pintype "passive"))
      (node (ref "U$95") (pin "2") (pinfunction "K_2") (pintype "bidirectional"))
    )
    (net (code "13") (name "/12_CATHODE") (class "Default")
      (node (ref "U$37") (pin "P$6") (pinfunction "6_P$6") (pintype "passive"))
      (node (ref "U$93") (pin "2") (pinfunction "K_2") (pintype "bidirectional"))
    )
    (net (code "14") (name "/13_CATHODE") (class "Default")
      (node (ref "U$35") (pin "P$5") (pinfunction "5_P$5") (pintype "passive"))
      (node (ref "U$91") (pin "2") (pinfunction "K_2") (pintype "bidirectional"))
    )
    (net (code "15") (name "/14_CATHODE") (class "Default")
      (node (ref "U$35") (pin "P$4") (pinfunction "4_P$4") (pintype "passive"))
      (node (ref "U$89") (pin "2") (pinfunction "K_2") (pintype "bidirectional"))
    )
    (net (code "16") (name "/15_CATHODE") (class "Default")
      (node (ref "U$35") (pin "P$3") (pinfunction "3_P$3") (pintype "passive"))
      (node (ref "U$87") (pin "2") (pinfunction "K_2") (pintype "bidirectional"))
    )
    (net (code "17") (name "/16_CATHODE") (class "Default")
      (node (ref "U$35") (pin "P$2") (pinfunction "2_P$2") (pintype "passive"))
      (node (ref "U$85") (pin "2") (pinfunction "K_2") (pintype "bidirectional"))
    )
    (net (code "18") (name "/17_CATHODE") (class "Default")
      (node (ref "U$34") (pin "P$9") (pinfunction "9_P$9") (pintype "passive"))
      (node (ref "U$83") (pin "2") (pinfunction "K_2") (pintype "bidirectional"))
    )
    (net (code "19") (name "/18_CATHODE") (class "Default")
      (node (ref "U$34") (pin "P$8") (pinfunction "8_P$8") (pintype "passive"))
      (node (ref "U$81") (pin "2") (pinfunction "K_2") (pintype "bidirectional"))
    )
    (net (code "20") (name "/19_CATHODE") (class "Default")
      (node (ref "U$34") (pin "P$7") (pinfunction "7_P$7") (pintype "passive"))
      (node (ref "U$79") (pin "2") (pinfunction "K_2") (pintype "bidirectional"))
    )
    (net (code "21") (name "/20_CATHODE") (class "Default")
      (node (ref "U$34") (pin "P$6") (pinfunction "6_P$6") (pintype "passive"))
      (node (ref "U$77") (pin "2") (pinfunction "K_2") (pintype "bidirectional"))
    )
    (net (code "22") (name "/21_CATHODE") (class "Default")
      (node (ref "U$34") (pin "P$5") (pinfunction "5_P$5") (pintype "passive"))
      (node (ref "U$75") (pin "2") (pinfunction "K_2") (pintype "bidirectional"))
    )
    (net (code "23") (name "/22_CATHODE") (class "Default")
      (node (ref "U$34") (pin "P$4") (pinfunction "4_P$4") (pintype "passive"))
      (node (ref "U$73") (pin "2") (pinfunction "K_2") (pintype "bidirectional"))
    )
    (net (code "24") (name "/23_CATHODE") (class "Default")
      (node (ref "U$34") (pin "P$3") (pinfunction "3_P$3") (pintype "passive"))
      (node (ref "U$71") (pin "2") (pinfunction "K_2") (pintype "bidirectional"))
    )
    (net (code "25") (name "/24_CATHODE") (class "Default")
      (node (ref "U$34") (pin "P$2") (pinfunction "2_P$2") (pintype "passive"))
      (node (ref "U$69") (pin "2") (pinfunction "K_2") (pintype "bidirectional"))
    )
    (net (code "26") (name "/A0") (class "Default")
      (node (ref "MS2") (pin "5") (pinfunction "GPIOA0_5") (pintype "bidirectional"))
      (node (ref "U4") (pin "15") (pinfunction "CLK_INH_15") (pintype "input"))
      (node (ref "U5") (pin "15") (pinfunction "CLK_INH_15") (pintype "input"))
      (node (ref "U6") (pin "15") (pinfunction "CLK_INH_15") (pintype "input"))
    )
    (net (code "27") (name "/A1") (class "Default")
      (node (ref "MS2") (pin "6") (pinfunction "GPIOA1_6") (pintype "bidirectional"))
      (node (ref "U1") (pin "15") (pinfunction "CLK_INH_15") (pintype "input"))
      (node (ref "U2") (pin "15") (pinfunction "CLK_INH_15") (pintype "input"))
      (node (ref "U3") (pin "15") (pinfunction "CLK_INH_15") (pintype "input"))
    )
    (net (code "28") (name "/A2") (class "Default")
      (node (ref "MS2") (pin "7") (pinfunction "GPIOA2_7") (pintype "bidirectional"))
    )
    (net (code "29") (name "/A3") (class "Default")
      (node (ref "MS2") (pin "8") (pinfunction "GPIOA3_8") (pintype "bidirectional"))
    )
    (net (code "30") (name "/A4") (class "Default")
      (node (ref "J3") (pin "1") (pinfunction "1_1") (pintype "passive"))
      (node (ref "MS2") (pin "9") (pinfunction "GPIOA4_9") (pintype "bidirectional"))
    )
    (net (code "34") (name "/D9") (class "Default")
      (node (ref "MS2") (pin "21") (pinfunction "GPIO9_21") (pintype "bidirectional"))
      (node (ref "Q7") (pin "1") (pinfunction "G_1") (pintype "bidirectional"))
      (node (ref "R15") (pin "P$2") (pinfunction "2_P$2") (pintype "passive"))
    )
    (net (code "35") (name "/D10") (class "Default")
      (node (ref "MS2") (pin "22") (pinfunction "GPIO10_22") (pintype "bidirectional"))
      (node (ref "Q6") (pin "1") (pinfunction "G_1") (pintype "bidirectional"))
      (node (ref "R13") (pin "P$2") (pinfunction "2_P$2") (pintype "passive"))
    )
    (net (code "39") (name "/LOAD") (class "Default")
      (node (ref "MS2") (pin "10") (pinfunction "GPIOA5_10") (pintype "bidirectional"))
      (node (ref "U1") (pin "1") (pinfunction "SH/~{LD}_1") (pintype "input"))
      (node (ref "U2") (pin "1") (pinfunction "SH/~{LD}_1") (pintype "input"))
      (node (ref "U3") (pin "1") (pinfunction "SH/~{LD}_1") (pintype "input"))
      (node (ref "U4") (pin "1") (pinfunction "SH/~{LD}_1") (pintype "input"))
      (node (ref "U5") (pin "1") (pinfunction "SH/~{LD}_1") (pintype "input"))
      (node (ref "U6") (pin "1") (pinfunction "SH/~{LD}_1") (pintype "input"))
    )
    (net (code "40") (name "/MISO") (class "Default")
      (node (ref "MS2") (pin "13") (pinfunction "GPIOMISO_13") (pintype "bidirectional"))
      (node (ref "U3") (pin "9") (pinfunction "QH_9") (pintype "tri_state"))
      (node (ref "U6") (pin "9") (pinfunction "QH_9") (pintype "tri_state"))
    )
    (net (code "41") (name "/MOSI") (class "Default")
      (node (ref "MS2") (pin "12") (pinfunction "GPIOMOSI_12") (pintype "bidirectional"))
    )
    (net (code "43") (name "/SCK") (class "Default")
      (node (ref "MS2") (pin "11") (pinfunction "GPIOSCK_11") (pintype "bidirectional"))
      (node (ref "U1") (pin "2") (pinfunction "CLK_2") (pintype "input"))
      (node (ref "U2") (pin "2") (pinfunction "CLK_2") (pintype "input"))
      (node (ref "U3") (pin "2") (pinfunction "CLK_2") (pintype "input"))
      (node (ref "U4") (pin "2") (pinfunction "CLK_2") (pintype "input"))
      (node (ref "U5") (pin "2") (pinfunction "CLK_2") (pintype "input"))
      (node (ref "U6") (pin "2") (pinfunction "CLK_2") (pintype "input"))
    )
    (net (code "44") (name "/SCL") (class "Default")
      (node (ref "J4") (pin "2") (pinfunction "2_2") (pintype "passive"))
      (node (ref "MS2") (pin "18") (pinfunction "GPIOSCL_18") (pintype "bidirectional"))
    )
    (net (code "45") (name "/SDA") (class "Default")
      (node (ref "J4") (pin "1") (pinfunction "1_1") (pintype "passive"))
      (node (ref "MS2") (pin "17") (pinfunction "GPIOSDA_17") (pintype "bidirectional"))
    )
    (net (code "46") (name "/SER1") (class "Default")
      (node (ref "U5") (pin "9") (pinfunction "QH_9") (pintype "tri_state"))
      (node (ref "U6") (pin "10") (pinfunction "SER_10") (pintype "input"))
    )
    (net (code "47") (name "/SER2") (class "Default")
      (node (ref "U4") (pin "9") (pinfunction "QH_9") (pintype "tri_state"))
      (node (ref "U5") (pin "10") (pinfunction "SER_10") (pintype "input"))
    )
    (net (code "48") (name "/SER3") (class "Default")
      (node (ref "U2") (pin "9") (pinfunction "QH_9") (pintype "tri_state"))
      (node (ref "U3") (pin "10") (pinfunction "SER_10") (pintype "input"))
    )
    (net (code "49") (name "/SER4") (class "Default")
      (node (ref "U1") (pin "9") (pinfunction "QH_9") (pintype "tri_state"))
      (node (ref "U2") (pin "10") (pinfunction "SER_10") (pintype "input"))
    )
    (net (code "51") (name "/VBAT") (class "Default")
      (node (ref "MS2") (pin "28") (pinfunction "VBAT_28") (pintype "power_in"))
    )
    (net (code "52") (name "3.3V") (class "Default")
      (node (ref "C1") (pin "1") (pinfunction "1_1") (pintype "passive"))
      (node (ref "C2") (pin "1") (pinfunction "1_1") (pintype "passive"))
      (node (ref "C3") (pin "1") (pinfunction "1_1") (pintype "passive"))
      (node (ref "C4") (pin "1") (pinfunction "1_1") (pintype "passive"))
      (node (ref "C5") (pin "1") (pinfunction "1_1") (pintype "passive"))
      (node (ref "C6") (pin "1") (pinfunction "1_1") (pintype "passive"))
      (node (ref "C8") (pin "+") (pinfunction "+_+") (pintype "passive"))
      (node (ref "J3") (pin "2") (pinfunction "2_2") (pintype "passive"))
      (node (ref "U$100") (pin "1") (pinfunction "A_1") (pintype "bidirectional"))
      (node (ref "U$100") (pin "3") (pinfunction "C_3") (pintype "bidirectional"))
      (node (ref "U$101") (pin "3") (pinfunction "C_3") (pintype "bidirectional"))
      (node (ref "U$102") (pin "1") (pinfunction "A_1") (pintype "bidirectional"))
      (node (ref "U$102") (pin "3") (pinfunction "C_3") (pintype "bidirectional"))
      (node (ref "U$103") (pin "3") (pinfunction "C_3") (pintype "bidirectional"))
      (node (ref "U$104") (pin "1") (pinfunction "A_1") (pintype "bidirectional"))
      (node (ref "U$104") (pin "3") (pinfunction "C_3") (pintype "bidirectional"))
      (node (ref "U$105") (pin "3") (pinfunction "C_3") (pintype "bidirectional"))
      (node (ref "U$106") (pin "1") (pinfunction "A_1") (pintype "bidirectional"))
      (node (ref "U$106") (pin "3") (pinfunction "C_3") (pintype "bidirectional"))
      (node (ref "U$107") (pin "3") (pinfunction "C_3") (pintype "bidirectional"))
      (node (ref "U$108") (pin "1") (pinfunction "A_1") (pintype "bidirectional"))
      (node (ref "U$108") (pin "3") (pinfunction "C_3") (pintype "bidirectional"))
      (node (ref "U$109") (pin "3") (pinfunction "C_3") (pintype "bidirectional"))
      (node (ref "U$110") (pin "1") (pinfunction "A_1") (pintype "bidirectional"))
      (node (ref "U$110") (pin "3") (pinfunction "C_3") (pintype "bidirectional"))
      (node (ref "U$111") (pin "3") (pinfunction "C_3") (pintype "bidirectional"))
      (node (ref "U$112") (pin "1") (pinfunction "A_1") (pintype "bidirectional"))
      (node (ref "U$112") (pin "3") (pinfunction "C_3") (pintype "bidirectional"))
      (node (ref "U$113") (pin "3") (pinfunction "C_3") (pintype "bidirectional"))
      (node (ref "U$114") (pin "1") (pinfunction "A_1") (pintype "bidirectional"))
      (node (ref "U$114") (pin "3") (pinfunction "C_3") (pintype "bidirectional"))
      (node (ref "U$115") (pin "3") (pinfunction "C_3") (pintype "bidirectional"))
      (node (ref "U$39") (pin "1") (pinfunction "1_1") (pintype "passive"))
      (node (ref "U$68") (pin "1") (pinfunction "A_1") (pintype "bidirectional"))
      (node (ref "U$68") (pin "3") (pinfunction "C_3") (pintype "bidirectional"))
      (node (ref "U$69") (pin "3") (pinfunction "C_3") (pintype "bidirectional"))
      (node (ref "U$70") (pin "1") (pinfunction "A_1") (pintype "bidirectional"))
      (node (ref "U$70") (pin "3") (pinfunction "C_3") (pintype "bidirectional"))
      (node (ref "U$71") (pin "3") (pinfunction "C_3") (pintype "bidirectional"))
      (node (ref "U$72") (pin "1") (pinfunction "A_1") (pintype "bidirectional"))
      (node (ref "U$72") (pin "3") (pinfunction "C_3") (pintype "bidirectional"))
      (node (ref "U$73") (pin "3") (pinfunction "C_3") (pintype "bidirectional"))
      (node (ref "U$74") (pin "1") (pinfunction "A_1") (pintype "bidirectional"))
      (node (ref "U$74") (pin "3") (pinfunction "C_3") (pintype "bidirectional"))
      (node (ref "U$75") (pin "3") (pinfunction "C_3") (pintype "bidirectional"))
      (node (ref "U$76") (pin "1") (pinfunction "A_1") (pintype "bidirectional"))
      (node (ref "U$76") (pin "3") (pinfunction "C_3") (pintype "bidirectional"))
      (node (ref "U$77") (pin "3") (pinfunction "C_3") (pintype "bidirectional"))
      (node (ref "U$78") (pin "1") (pinfunction "A_1") (pintype "bidirectional"))
      (node (ref "U$78") (pin "3") (pinfunction "C_3") (pintype "bidirectional"))
      (node (ref "U$79") (pin "3") (pinfunction "C_3") (pintype "bidirectional"))
      (node (ref "U$80") (pin "1") (pinfunction "A_1") (pintype "bidirectional"))
      (node (ref "U$80") (pin "3") (pinfunction "C_3") (pintype "bidirectional"))
      (node (ref "U$81") (pin "3") (pinfunction "C_3") (pintype "bidirectional"))
      (node (ref "U$82") (pin "1") (pinfunction "A_1") (pintype "bidirectional"))
      (node (ref "U$82") (pin "3") (pinfunction "C_3") (pintype "bidirectional"))
      (node (ref "U$83") (pin "3") (pinfunction "C_3") (pintype "bidirectional"))
      (node (ref "U$84") (pin "1") (pinfunction "A_1") (pintype "bidirectional"))
      (node (ref "U$84") (pin "3") (pinfunction "C_3") (pintype "bidirectional"))
      (node (ref "U$85") (pin "3") (pinfunction "C_3") (pintype "bidirectional"))
      (node (ref "U$86") (pin "1") (pinfunction "A_1") (pintype "bidirectional"))
      (node (ref "U$86") (pin "3") (pinfunction "C_3") (pintype "bidirectional"))
      (node (ref "U$87") (pin "3") (pinfunction "C_3") (pintype "bidirectional"))
      (node (ref "U$88") (pin "1") (pinfunction "A_1") (pintype "bidirectional"))
      (node (ref "U$88") (pin "3") (pinfunction "C_3") (pintype "bidirectional"))
      (node (ref "U$89") (pin "3") (pinfunction "C_3") (pintype "bidirectional"))
      (node (ref "U$90") (pin "1") (pinfunction "A_1") (pintype "bidirectional"))
      (node (ref "U$90") (pin "3") (pinfunction "C_3") (pintype "bidirectional"))
      (node (ref "U$91") (pin "3") (pinfunction "C_3") (pintype "bidirectional"))
      (node (ref "U$92") (pin "1") (pinfunction "A_1") (pintype "bidirectional"))
      (node (ref "U$92") (pin "3") (pinfunction "C_3") (pintype "bidirectional"))
      (node (ref "U$93") (pin "3") (pinfunction "C_3") (pintype "bidirectional"))
      (node (ref "U$94") (pin "1") (pinfunction "A_1") (pintype "bidirectional"))
      (node (ref "U$94") (pin "3") (pinfunction "C_3") (pintype "bidirectional"))
      (node (ref "U$95") (pin "3") (pinfunction "C_3") (pintype "bidirectional"))
      (node (ref "U$96") (pin "1") (pinfunction "A_1") (pintype "bidirectional"))
      (node (ref "U$96") (pin "3") (pinfunction "C_3") (pintype "bidirectional"))
      (node (ref "U$97") (pin "3") (pinfunction "C_3") (pintype "bidirectional"))
      (node (ref "U$98") (pin "1") (pinfunction "A_1") (pintype "bidirectional"))
      (node (ref "U$98") (pin "3") (pinfunction "C_3") (pintype "bidirectional"))
      (node (ref "U$99") (pin "3") (pinfunction "C_3") (pintype "bidirectional"))
      (node (ref "U1") (pin "16") (pinfunction "VCC_16") (pintype "power_in"))
      (node (ref "U2") (pin "16") (pinfunction "VCC_16") (pintype "power_in"))
      (node (ref "U3") (pin "16") (pinfunction "VCC_16") (pintype "power_in"))
      (node (ref "U4") (pin "16") (pinfunction "VCC_16") (pintype "power_in"))
      (node (ref "U5") (pin "16") (pinfunction "VCC_16") (pintype "power_in"))
      (node (ref "U6") (pin "16") (pinfunction "VCC_16") (pintype "power_in"))
      (node (ref "U7") (pin "OUT") (pinfunction "OUT_OUT") (pintype "passive"))
    )
    (net (code "53") (name "5V") (class "Default")
      (node (ref "C7") (pin "1") (pinfunction "1_1") (pintype "passive"))
      (node (ref "J1") (pin "2") (pinfunction "2_2") (pintype "passive"))
      (node (ref "JP1") (pin "1") (pinfunction "1_1") (pintype "passive"))
      (node (ref "U$40") (pin "1") (pinfunction "1_1") (pintype "passive"))
      (node (ref "U7") (pin "IN") (pinfunction "IN_IN") (pintype "input"))
    )
    (net (code "54") (name "GND") (class "Default")
      (node (ref "C1") (pin "2") (pinfunction "2_2") (pintype "passive"))
      (node (ref "C2") (pin "2") (pinfunction "2_2") (pintype "passive"))
      (node (ref "C3") (pin "2") (pinfunction "2_2") (pintype "passive"))
      (node (ref "C4") (pin "2") (pinfunction "2_2") (pintype "passive"))
      (node (ref "C5") (pin "2") (pinfunction "2_2") (pintype "passive"))
      (node (ref "C6") (pin "2") (pinfunction "2_2") (pintype "passive"))
      (node (ref "C7") (pin "2") (pinfunction "2_2") (pintype "passive"))
      (node (ref "C8") (pin "-") (pinfunction "-_-") (pintype "passive"))
      (node (ref "J1") (pin "1") (pinfunction "1_1") (pintype "passive"))
      (node (ref "MS2") (pin "4") (pinfunction "GND_4") (pintype "power_in"))
      (node (ref "Q6") (pin "3") (pinfunction "S_3") (pintype "bidirectional"))
      (node (ref "Q7") (pin "3") (pinfunction "S_3") (pintype "bidirectional"))
      (node (ref "R11") (pin "P$1") (pinfunction "1_P$1") (pintype "passive"))
      (node (ref "R12") (pin "P$1") (pinfunction "1_P$1") (pintype "passive"))
      (node (ref "R13") (pin "P$1") (pinfunction "1_P$1") (pintype "passive"))
      (node (ref "R15") (pin "P$1") (pinfunction "1_P$1") (pintype "passive"))
      (node (ref "R2") (pin "P$1") (pinfunction "1_P$1") (pintype "passive"))
      (node (ref "R5") (pin "P$1") (pinfunction "1_P$1") (pintype "passive"))
      (node (ref "R6") (pin "P$1") (pinfunction "1_P$1") (pintype "passive"))
      (node (ref "R7") (pin "P$1") (pinfunction "1_P$1") (pintype "passive"))
      (node (ref "S1") (pin "P1") (pinfunction "P$1_P1") (pintype "bidirectional"))
      (node (ref "S2") (pin "P1") (pinfunction "P$1_P1") (pintype "bidirectional"))
      (node (ref "U$31") (pin "1") (pinfunction "1_1") (pintype "passive"))
      (node (ref "U1") (pin "8") (pinfunction "GND_8") (pintype "power_in"))
      (node (ref "U2") (pin "8") (pinfunction "GND_8") (pintype "power_in"))
      (node (ref "U3") (pin "8") (pinfunction "GND_8") (pintype "power_in"))
      (node (ref "U4") (pin "8") (pinfunction "GND_8") (pintype "power_in"))
      (node (ref "U5") (pin "8") (pinfunction "GND_8") (pintype "power_in"))
      (node (ref "U6") (pin "8") (pinfunction "GND_8") (pintype "power_in"))
      (node (ref "U7") (pin "GND") (pinfunction "GND_GND") (pintype "input"))
    )
    (net (code "55") (name "Net-(MS2-USB)") (class "Default")
      (node (ref "JP1") (pin "2") (pinfunction "2_2") (pintype "passive"))
      (node (ref "MS2") (pin "26") (pinfunction "USB_26") (pintype "power_in"))
    )
    (net (code "56") (name "Net-(Q6-D)") (class "Default")
      (node (ref "Q6") (pin "2") (pinfunction "D_2") (pintype "bidirectional"))
      (node (ref "U$34") (pin "P$1") (pinfunction "1_P$1") (pintype "passive"))
      (node (ref "U$35") (pin "P$1") (pinfunction "1_P$1") (pintype "passive"))
    )
    (net (code "57") (name "Net-(Q7-D)") (class "Default")
      (node (ref "Q7") (pin "2") (pinfunction "D_2") (pintype "bidirectional"))
      (node (ref "U$36") (pin "P$1") (pinfunction "1_P$1") (pintype "passive"))
      (node (ref "U$37") (pin "P$1") (pinfunction "1_P$1") (pintype "passive"))
    )
    (net (code "58") (name "Net-(R2-2)") (class "Default")
      (node (ref "R2") (pin "P$2") (pinfunction "2_P$2") (pintype "passive"))
      (node (ref "U$70") (pin "4") (pinfunction "E_4") (pintype "bidirectional"))
      (node (ref "U1") (pin "3") (pinfunction "E_3") (pintype "tri_state"))
    )
    (net (code "59") (name "Net-(R2-3)") (class "Default")
      (node (ref "R2") (pin "P$3") (pinfunction "3_P$3") (pintype "passive"))
      (node (ref "U$71") (pin "4") (pinfunction "E_4") (pintype "bidirectional"))
      (node (ref "U1") (pin "4") (pinfunction "F_4") (pintype "tri_state"))
    )
    (net (code "60") (name "Net-(R2-4)") (class "Default")
      (node (ref "R2") (pin "P$4") (pinfunction "4_P$4") (pintype "passive"))
      (node (ref "U$69") (pin "4") (pinfunction "E_4") (pintype "bidirectional"))
      (node (ref "U1") (pin "6") (pinfunction "H_6") (pintype "tri_state"))
    )
    (net (code "61") (name "Net-(R2-5)") (class "Default")
      (node (ref "R2") (pin "P$5") (pinfunction "5_P$5") (pintype "passive"))
      (node (ref "U$68") (pin "4") (pinfunction "E_4") (pintype "bidirectional"))
      (node (ref "U1") (pin "5") (pinfunction "G_5") (pintype "tri_state"))
    )
    (net (code "62") (name "Net-(R2-6)") (class "Default")
      (node (ref "R2") (pin "P$6") (pinfunction "6_P$6") (pintype "passive"))
      (node (ref "U$73") (pin "4") (pinfunction "E_4") (pintype "bidirectional"))
      (node (ref "U1") (pin "14") (pinfunction "D_14") (pintype "tri_state"))
    )
    (net (code "63") (name "Net-(R2-7)") (class "Default")
      (node (ref "R2") (pin "P$7") (pinfunction "7_P$7") (pintype "passive"))
      (node (ref "U$72") (pin "4") (pinfunction "E_4") (pintype "bidirectional"))
      (node (ref "U1") (pin "13") (pinfunction "C_13") (pintype "tri_state"))
    )
    (net (code "64") (name "Net-(R2-8)") (class "Default")
      (node (ref "R2") (pin "P$8") (pinfunction "8_P$8") (pintype "passive"))
      (node (ref "U$75") (pin "4") (pinfunction "E_4") (pintype "bidirectional"))
      (node (ref "U1") (pin "12") (pinfunction "B_12") (pintype "tri_state"))
    )
    (net (code "65") (name "Net-(R2-9)") (class "Default")
      (node (ref "R2") (pin "P$9") (pinfunction "9_P$9") (pintype "passive"))
      (node (ref "U$74") (pin "4") (pinfunction "E_4") (pintype "bidirectional"))
      (node (ref "U1") (pin "11") (pinfunction "A_11") (pintype "tri_state"))
    )
    (net (code "66") (name "Net-(R5-2)") (class "Default")
      (node (ref "R5") (pin "P$2") (pinfunction "2_P$2") (pintype "passive"))
      (node (ref "U$82") (pin "4") (pinfunction "E_4") (pintype "bidirectional"))
      (node (ref "U2") (pin "11") (pinfunction "A_11") (pintype "tri_state"))
    )
    (net (code "67") (name "Net-(R5-3)") (class "Default")
      (node (ref "R5") (pin "P$3") (pinfunction "3_P$3") (pintype "passive"))
      (node (ref "U$83") (pin "4") (pinfunction "E_4") (pintype "bidirectional"))
      (node (ref "U2") (pin "12") (pinfunction "B_12") (pintype "tri_state"))
    )
    (net (code "68") (name "Net-(R5-4)") (class "Default")
      (node (ref "R5") (pin "P$4") (pinfunction "4_P$4") (pintype "passive"))
      (node (ref "U$80") (pin "4") (pinfunction "E_4") (pintype "bidirectional"))
      (node (ref "U2") (pin "13") (pinfunction "C_13") (pintype "tri_state"))
    )
    (net (code "69") (name "Net-(R5-5)") (class "Default")
      (node (ref "R5") (pin "P$5") (pinfunction "5_P$5") (pintype "passive"))
      (node (ref "U$81") (pin "4") (pinfunction "E_4") (pintype "bidirectional"))
      (node (ref "U2") (pin "14") (pinfunction "D_14") (pintype "tri_state"))
    )
    (net (code "70") (name "Net-(R5-6)") (class "Default")
      (node (ref "R5") (pin "P$6") (pinfunction "6_P$6") (pintype "passive"))
      (node (ref "U$78") (pin "4") (pinfunction "E_4") (pintype "bidirectional"))
      (node (ref "U2") (pin "3") (pinfunction "E_3") (pintype "tri_state"))
    )
    (net (code "71") (name "Net-(R5-7)") (class "Default")
      (node (ref "R5") (pin "P$7") (pinfunction "7_P$7") (pintype "passive"))
      (node (ref "U$79") (pin "4") (pinfunction "E_4") (pintype "bidirectional"))
      (node (ref "U2") (pin "4") (pinfunction "F_4") (pintype "tri_state"))
    )
    (net (code "72") (name "Net-(R5-8)") (class "Default")
      (node (ref "R5") (pin "P$8") (pinfunction "8_P$8") (pintype "passive"))
      (node (ref "U$76") (pin "4") (pinfunction "E_4") (pintype "bidirectional"))
      (node (ref "U2") (pin "5") (pinfunction "G_5") (pintype "tri_state"))
    )
    (net (code "73") (name "Net-(R5-9)") (class "Default")
      (node (ref "R5") (pin "P$9") (pinfunction "9_P$9") (pintype "passive"))
      (node (ref "U$77") (pin "4") (pinfunction "E_4") (pintype "bidirectional"))
      (node (ref "U2") (pin "6") (pinfunction "H_6") (pintype "tri_state"))
    )
    (net (code "74") (name "Net-(R6-2)") (class "Default")
      (node (ref "R6") (pin "P$2") (pinfunction "2_P$2") (pintype "passive"))
      (node (ref "U$91") (pin "4") (pinfunction "E_4") (pintype "bidirectional"))
      (node (ref "U3") (pin "12") (pinfunction "B_12") (pintype "tri_state"))
    )
    (net (code "75") (name "Net-(R6-3)") (class "Default")
      (node (ref "R6") (pin "P$3") (pinfunction "3_P$3") (pintype "passive"))
      (node (ref "U$90") (pin "4") (pinfunction "E_4") (pintype "bidirectional"))
      (node (ref "U3") (pin "11") (pinfunction "A_11") (pintype "tri_state"))
    )
    (net (code "76") (name "Net-(R6-4)") (class "Default")
      (node (ref "R6") (pin "P$4") (pinfunction "4_P$4") (pintype "passive"))
      (node (ref "U$88") (pin "4") (pinfunction "E_4") (pintype "bidirectional"))
      (node (ref "U3") (pin "13") (pinfunction "C_13") (pintype "tri_state"))
    )
    (net (code "77") (name "Net-(R6-5)") (class "Default")
      (node (ref "R6") (pin "P$5") (pinfunction "5_P$5") (pintype "passive"))
      (node (ref "U$89") (pin "4") (pinfunction "E_4") (pintype "bidirectional"))
      (node (ref "U3") (pin "14") (pinfunction "D_14") (pintype "tri_state"))
    )
    (net (code "78") (name "Net-(R6-6)") (class "Default")
      (node (ref "R6") (pin "P$6") (pinfunction "6_P$6") (pintype "passive"))
      (node (ref "U$86") (pin "4") (pinfunction "E_4") (pintype "bidirectional"))
      (node (ref "U3") (pin "3") (pinfunction "E_3") (pintype "tri_state"))
    )
    (net (code "79") (name "Net-(R6-7)") (class "Default")
      (node (ref "R6") (pin "P$7") (pinfunction "7_P$7") (pintype "passive"))
      (node (ref "U$87") (pin "4") (pinfunction "E_4") (pintype "bidirectional"))
      (node (ref "U3") (pin "4") (pinfunction "F_4") (pintype "tri_state"))
    )
    (net (code "80") (name "Net-(R6-8)") (class "Default")
      (node (ref "R6") (pin "P$8") (pinfunction "8_P$8") (pintype "passive"))
      (node (ref "U$84") (pin "4") (pinfunction "E_4") (pintype "bidirectional"))
      (node (ref "U3") (pin "5") (pinfunction "G_5") (pintype "tri_state"))
    )
    (net (code "81") (name "Net-(R6-9)") (class "Default")
      (node (ref "R6") (pin "P$9") (pinfunction "9_P$9") (pintype "passive"))
      (node (ref "U$85") (pin "4") (pinfunction "E_4") (pintype "bidirectional"))
      (node (ref "U3") (pin "6") (pinfunction "H_6") (pintype "tri_state"))
    )
    (net (code "82") (name "Net-(R7-2)") (class "Default")
      (node (ref "R7") (pin "P$2") (pinfunction "2_P$2") (pintype "passive"))
      (node (ref "U$98") (pin "4") (pinfunction "E_4") (pintype "bidirectional"))
      (node (ref "U4") (pin "11") (pinfunction "A_11") (pintype "tri_state"))
    )
    (net (code "83") (name "Net-(R7-3)") (class "Default")
      (node (ref "R7") (pin "P$3") (pinfunction "3_P$3") (pintype "passive"))
      (node (ref "U$99") (pin "4") (pinfunction "E_4") (pintype "bidirectional"))
      (node (ref "U4") (pin "12") (pinfunction "B_12") (pintype "tri_state"))
    )
    (net (code "84") (name "Net-(R7-4)") (class "Default")
      (node (ref "R7") (pin "P$4") (pinfunction "4_P$4") (pintype "passive"))
      (node (ref "U$96") (pin "4") (pinfunction "E_4") (pintype "bidirectional"))
      (node (ref "U4") (pin "13") (pinfunction "C_13") (pintype "tri_state"))
    )
    (net (code "85") (name "Net-(R7-5)") (class "Default")
      (node (ref "R7") (pin "P$5") (pinfunction "5_P$5") (pintype "passive"))
      (node (ref "U$97") (pin "4") (pinfunction "E_4") (pintype "bidirectional"))
      (node (ref "U4") (pin "14") (pinfunction "D_14") (pintype "tri_state"))
    )
    (net (code "86") (name "Net-(R7-6)") (class "Default")
      (node (ref "R7") (pin "P$6") (pinfunction "6_P$6") (pintype "passive"))
      (node (ref "U$94") (pin "4") (pinfunction "E_4") (pintype "bidirectional"))
      (node (ref "U4") (pin "3") (pinfunction "E_3") (pintype "tri_state"))
    )
    (net (code "87") (name "Net-(R7-7)") (class "Default")
      (node (ref "R7") (pin "P$7") (pinfunction "7_P$7") (pintype "passive"))
      (node (ref "U$95") (pin "4") (pinfunction "E_4") (pintype "bidirectional"))
      (node (ref "U4") (pin "4") (pinfunction "F_4") (pintype "tri_state"))
    )
    (net (code "88") (name "Net-(R7-8)") (class "Default")
      (node (ref "R7") (pin "P$8") (pinfunction "8_P$8") (pintype "passive"))
      (node (ref "U$92") (pin "4") (pinfunction "E_4") (pintype "bidirectional"))
      (node (ref "U4") (pin "5") (pinfunction "G_5") (pintype "tri_state"))
    )
    (net (code "89") (name "Net-(R7-9)") (class "Default")
      (node (ref "R7") (pin "P$9") (pinfunction "9_P$9") (pintype "passive"))
      (node (ref "U$93") (pin "4") (pinfunction "E_4") (pintype "bidirectional"))
      (node (ref "U4") (pin "6") (pinfunction "H_6") (pintype "tri_state"))
    )
    (net (code "90") (name "Net-(R11-2)") (class "Default")
      (node (ref "R11") (pin "P$2") (pinfunction "2_P$2") (pintype "passive"))
      (node (ref "U$106") (pin "4") (pinfunction "E_4") (pintype "bidirectional"))
      (node (ref "U5") (pin "11") (pinfunction "A_11") (pintype "tri_state"))
    )
    (net (code "91") (name "Net-(R11-3)") (class "Default")
      (node (ref "R11") (pin "P$3") (pinfunction "3_P$3") (pintype "passive"))
      (node (ref "U$107") (pin "4") (pinfunction "E_4") (pintype "bidirectional"))
      (node (ref "U5") (pin "12") (pinfunction "B_12") (pintype "tri_state"))
    )
    (net (code "92") (name "Net-(R11-4)") (class "Default")
      (node (ref "R11") (pin "P$4") (pinfunction "4_P$4") (pintype "passive"))
      (node (ref "U$104") (pin "4") (pinfunction "E_4") (pintype "bidirectional"))
      (node (ref "U5") (pin "13") (pinfunction "C_13") (pintype "tri_state"))
    )
    (net (code "93") (name "Net-(R11-5)") (class "Default")
      (node (ref "R11") (pin "P$5") (pinfunction "5_P$5") (pintype "passive"))
      (node (ref "U$105") (pin "4") (pinfunction "E_4") (pintype "bidirectional"))
      (node (ref "U5") (pin "14") (pinfunction "D_14") (pintype "tri_state"))
    )
    (net (code "94") (name "Net-(R11-6)") (class "Default")
      (node (ref "R11") (pin "P$6") (pinfunction "6_P$6") (pintype "passive"))
      (node (ref "U$102") (pin "4") (pinfunction "E_4") (pintype "bidirectional"))
      (node (ref "U5") (pin "3") (pinfunction "E_3") (pintype "tri_state"))
    )
    (net (code "95") (name "Net-(R11-7)") (class "Default")
      (node (ref "R11") (pin "P$7") (pinfunction "7_P$7") (pintype "passive"))
      (node (ref "U$103") (pin "4") (pinfunction "E_4") (pintype "bidirectional"))
      (node (ref "U5") (pin "4") (pinfunction "F_4") (pintype "tri_state"))
    )
    (net (code "96") (name "Net-(R11-8)") (class "Default")
      (node (ref "R11") (pin "P$8") (pinfunction "8_P$8") (pintype "passive"))
      (node (ref "U$100") (pin "4") (pinfunction "E_4") (pintype "bidirectional"))
      (node (ref "U5") (pin "5") (pinfunction "G_5") (pintype "tri_state"))
    )
    (net (code "97") (name "Net-(R11-9)") (class "Default")
      (node (ref "R11") (pin "P$9") (pinfunction "9_P$9") (pintype "passive"))
      (node (ref "U$101") (pin "4") (pinfunction "E_4") (pintype "bidirectional"))
      (node (ref "U5") (pin "6") (pinfunction "H_6") (pintype "tri_state"))
    )
    (net (code "98") (name "Net-(R12-2)") (class "Default")
      (node (ref "R12") (pin "P$2") (pinfunction "2_P$2") (pintype "passive"))
      (node (ref "U$115") (pin "4") (pinfunction "E_4") (pintype "bidirectional"))
      (node (ref "U6") (pin "12") (pinfunction "B_12") (pintype "tri_state"))
    )
    (net (code "99") (name "Net-(R12-3)") (class "Default")
      (node (ref "R12") (pin "P$3") (pinfunction "3_P$3") (pintype "passive"))
      (node (ref "U$114") (pin "4") (pinfunction "E_4") (pintype "bidirectional"))
      (node (ref "U6") (pin "11") (pinfunction "A_11") (pintype "tri_state"))
    )
    (net (code "100") (name "Net-(R12-4)") (class "Default")
      (node (ref "R12") (pin "P$4") (pinfunction "4_P$4") (pintype "passive"))
      (node (ref "U$112") (pin "4") (pinfunction "E_4") (pintype "bidirectional"))
      (node (ref "U6") (pin "13") (pinfunction "C_13") (pintype "tri_state"))
    )
    (net (code "101") (name "Net-(R12-5)") (class "Default")
      (node (ref "R12") (pin "P$5") (pinfunction "5_P$5") (pintype "passive"))
      (node (ref "U$113") (pin "4") (pinfunction "E_4") (pintype "bidirectional"))
      (node (ref "U6") (pin "14") (pinfunction "D_14") (pintype "tri_state"))
    )
    (net (code "102") (name "Net-(R12-6)") (class "Default")
      (node (ref "R12") (pin "P$6") (pinfunction "6_P$6") (pintype "passive"))
      (node (ref "U$110") (pin "4") (pinfunction "E_4") (pintype "bidirectional"))
      (node (ref "U6") (pin "3") (pinfunction "E_3") (pintype "tri_state"))
    )
    (net (code "103") (name "Net-(R12-7)") (class "Default")
      (node (ref "R12") (pin "P$7") (pinfunction "7_P$7") (pintype "passive"))
      (node (ref "U$111") (pin "4") (pinfunction "E_4") (pintype "bidirectional"))
      (node (ref "U6") (pin "4") (pinfunction "F_4") (pintype "tri_state"))
    )
    (net (code "104") (name "Net-(R12-8)") (class "Default")
      (node (ref "R12") (pin "P$8") (pinfunction "8_P$8") (pintype "passive"))
      (node (ref "U$108") (pin "4") (pinfunction "E_4") (pintype "bidirectional"))
      (node (ref "U6") (pin "5") (pinfunction "G_5") (pintype "tri_state"))
    )
    (net (code "105") (name "Net-(R12-9)") (class "Default")
      (node (ref "R12") (pin "P$9") (pinfunction "9_P$9") (pintype "passive"))
      (node (ref "U$109") (pin "4") (pinfunction "E_4") (pintype "bidirectional"))
      (node (ref "U6") (pin "6") (pinfunction "H_6") (pintype "tri_state"))
    )
    (net (code "106") (name "Net-(U$68-K)") (class "Default")
      (node (ref "U$68") (pin "2") (pinfunction "K_2") (pintype "bidirectional"))
      (node (ref "U$69") (pin "1") (pinfunction "A_1") (pintype "bidirectional"))
    )
    (net (code "107") (name "Net-(U$70-K)") (class "Default")
      (node (ref "U$70") (pin "2") (pinfunction "K_2") (pintype "bidirectional"))
      (node (ref "U$71") (pin "1") (pinfunction "A_1") (pintype "bidirectional"))
    )
    (net (code "108") (name "Net-(U$72-K)") (class "Default")
      (node (ref "U$72") (pin "2") (pinfunction "K_2") (pintype "bidirectional"))
      (node (ref "U$73") (pin "1") (pinfunction "A_1") (pintype "bidirectional"))
    )
    (net (code "109") (name "Net-(U$74-K)") (class "Default")
      (node (ref "U$74") (pin "2") (pinfunction "K_2") (pintype "bidirectional"))
      (node (ref "U$75") (pin "1") (pinfunction "A_1") (pintype "bidirectional"))
    )
    (net (code "110") (name "Net-(U$76-K)") (class "Default")
      (node (ref "U$76") (pin "2") (pinfunction "K_2") (pintype "bidirectional"))
      (node (ref "U$77") (pin "1") (pinfunction "A_1") (pintype "bidirectional"))
    )
    (net (code "111") (name "Net-(U$78-K)") (class "Default")
      (node (ref "U$78") (pin "2") (pinfunction "K_2") (pintype "bidirectional"))
      (node (ref "U$79") (pin "1") (pinfunction "A_1") (pintype "bidirectional"))
    )
    (net (code "112") (name "Net-(U$80-K)") (class "Default")
      (node (ref "U$80") (pin "2") (pinfunction "K_2") (pintype "bidirectional"))
      (node (ref "U$81") (pin "1") (pinfunction "A_1") (pintype "bidirectional"))
    )
    (net (code "113") (name "Net-(U$82-K)") (class "Default")
      (node (ref "U$82") (pin "2") (pinfunction "K_2") (pintype "bidirectional"))
      (node (ref "U$83") (pin "1") (pinfunction "A_1") (pintype "bidirectional"))
    )
    (net (code "114") (name "Net-(U$84-K)") (class "Default")
      (node (ref "U$84") (pin "2") (pinfunction "K_2") (pintype "bidirectional"))
      (node (ref "U$85") (pin "1") (pinfunction "A_1") (pintype "bidirectional"))
    )
    (net (code "115") (name "Net-(U$86-K)") (class "Default")
      (node (ref "U$86") (pin "2") (pinfunction "K_2") (pintype "bidirectional"))
      (node (ref "U$87") (pin "1") (pinfunction "A_1") (pintype "bidirectional"))
    )
    (net (code "116") (name "Net-(U$88-K)") (class "Default")
      (node (ref "U$88") (pin "2") (pinfunction "K_2") (pintype "bidirectional"))
      (node (ref "U$89") (pin "1") (pinfunction "A_1") (pintype "bidirectional"))
    )
    (net (code "117") (name "Net-(U$90-K)") (class "Default")
      (node (ref "U$90") (pin "2") (pinfunction "K_2") (pintype "bidirectional"))
      (node (ref "U$91") (pin "1") (pinfunction "A_1") (pintype "bidirectional"))
    )
    (net (code "118") (name "Net-(U$92-K)") (class "Default")
      (node (ref "U$92") (pin "2") (pinfunction "K_2") (pintype "bidirectional"))
      (node (ref "U$93") (pin "1") (pinfunction "A_1") (pintype "bidirectional"))
    )
    (net (code "119") (name "Net-(U$94-K)") (class "Default")
      (node (ref "U$94") (pin "2") (pinfunction "K_2") (pintype "bidirectional"))
      (node (ref "U$95") (pin "1") (pinfunction "A_1") (pintype "bidirectional"))
    )
    (net (code "120") (name "Net-(U$96-K)") (class "Default")
      (node (ref "U$96") (pin "2") (pinfunction "K_2") (pintype "bidirectional"))
      (node (ref "U$97") (pin "1") (pinfunction "A_1") (pintype "bidirectional"))
    )
    (net (code "121") (name "Net-(U$98-K)") (class "Default")
      (node (ref "U$98") (pin "2") (pinfunction "K_2") (pintype "bidirectional"))
      (node (ref "U$99") (pin "1") (pinfunction "A_1") (pintype "bidirectional"))
    )
    (net (code "122") (name "Net-(U$100-K)") (class "Default")
      (node (ref "U$100") (pin "2") (pinfunction "K_2") (pintype "bidirectional"))
      (node (ref "U$101") (pin "1") (pinfunction "A_1") (pintype "bidirectional"))
    )
    (net (code "123") (name "Net-(U$102-K)") (class "Default")
      (node (ref "U$102") (pin "2") (pinfunction "K_2") (pintype "bidirectional"))
      (node (ref "U$103") (pin "1") (pinfunction "A_1") (pintype "bidirectional"))
    )
    (net (code "124") (name "Net-(U$104-K)") (class "Default")
      (node (ref "U$104") (pin "2") (pinfunction "K_2") (pintype "bidirectional"))
      (node (ref "U$105") (pin "1") (pinfunction "A_1") (pintype "bidirectional"))
    )
    (net (code "125") (name "Net-(U$106-K)") (class "Default")
      (node (ref "U$106") (pin "2") (pinfunction "K_2") (pintype "bidirectional"))
      (node (ref "U$107") (pin "1") (pinfunction "A_1") (pintype "bidirectional"))
    )
    (net (code "126") (name "Net-(U$108-K)") (class "Default")
      (node (ref "U$108") (pin "2") (pinfunction "K_2") (pintype "bidirectional"))
      (node (ref "U$109") (pin "1") (pinfunction "A_1") (pintype "bidirectional"))
    )
    (net (code "127") (name "Net-(U$110-K)") (class "Default")
      (node (ref "U$110") (pin "2") (pinfunction "K_2") (pintype "bidirectional"))
      (node (ref "U$111") (pin "1") (pinfunction "A_1") (pintype "bidirectional"))
    )
    (net (code "128") (name "Net-(U$112-K)") (class "Default")
      (node (ref "U$112") (pin "2") (pinfunction "K_2") (pintype "bidirectional"))
      (node (ref "U$113") (pin "1") (pinfunction "A_1") (pintype "bidirectional"))
    )
    (net (code "129") (name "Net-(U$114-K)") (class "Default")
      (node (ref "U$114") (pin "2") (pinfunction "K_2") (pintype "bidirectional"))
      (node (ref "U$115") (pin "1") (pinfunction "A_1") (pintype "bidirectional"))
    )
    (net (code "130") (name "unconnected-(MS2-AREF-Pad3)") (class "Default")
      (node (ref "MS2") (pin "3") (pinfunction "AREF_3") (pintype "passive"))
    )
    (net (code "131") (name "unconnected-(MS2-EN-Pad27)") (class "Default")
      (node (ref "MS2") (pin "27") (pinfunction "EN_27") (pintype "passive"))
    )
    (net (code "132") (name "unconnected-(MS2-GPIO5-Pad19)") (class "Default")
      (node (ref "MS2") (pin "19") (pinfunction "GPIO5_19") (pintype "bidirectional"))
    )
    (net (code "133") (name "unconnected-(MS2-GPIO6-Pad20)") (class "Default")
      (node (ref "MS2") (pin "20") (pinfunction "GPIO6_20") (pintype "bidirectional"))
    )
    (net (code "134") (name "unconnected-(MS2-GPIO11-Pad23)") (class "Default")
      (node (ref "MS2") (pin "23") (pinfunction "GPIO11_23") (pintype "bidirectional"))
    )
    (net (code "135") (name "unconnected-(MS2-GPIO12-Pad24)") (class "Default")
      (node (ref "MS2") (pin "24") (pinfunction "GPIO12_24") (pintype "bidirectional"))
    )
    (net (code "136") (name "unconnected-(MS2-GPIO13-Pad25)") (class "Default")
      (node (ref "MS2") (pin "25") (pinfunction "GPIO13_25") (pintype "bidirectional"))
    )
    (net (code "137") (name "unconnected-(MS2-GPIORX-Pad14)") (class "Default")
      (node (ref "MS2") (pin "14") (pinfunction "GPIORX_14") (pintype "bidirectional"))
    )
    (net (code "138") (name "unconnected-(MS2-GPIOTX-Pad15)") (class "Default")
      (node (ref "MS2") (pin "15") (pinfunction "GPIOTX_15") (pintype "bidirectional"))
    )
    (net (code "139") (name "unconnected-(MS2-NC-Pad16)") (class "Default")
      (node (ref "MS2") (pin "16") (pinfunction "NC_16") (pintype "passive"))
    )
    (net (code "140") (name "unconnected-(MS2-~{RESET}-Pad1)") (class "Default")
      (node (ref "MS2") (pin "1") (pinfunction "~{RESET}_1") (pintype "input"))
    )
    (net (code "141") (name "unconnected-(U$1-4-Pad1)") (class "Default")
      (node (ref "U$1") (pin "1") (pinfunction "4_1") (pintype "passive"))
    )
    (net (code "142") (name "unconnected-(U$1-Pad6)") (class "Default")
      (node (ref "U$1") (pin "6") (pinfunction "6_6") (pintype "passive"))
    )
    (net (code "143") (name "unconnected-(U$2-4-Pad1)") (class "Default")
      (node (ref "U$2") (pin "1") (pinfunction "4_1") (pintype "passive"))
    )
    (net (code "144") (name "unconnected-(U$2-Pad6)") (class "Default")
      (node (ref "U$2") (pin "6") (pinfunction "6_6") (pintype "passive"))
    )
    (net (code "145") (name "unconnected-(U$3-4-Pad1)") (class "Default")
      (node (ref "U$3") (pin "1") (pinfunction "4_1") (pintype "passive"))
    )
    (net (code "146") (name "unconnected-(U$3-Pad6)") (class "Default")
      (node (ref "U$3") (pin "6") (pinfunction "6_6") (pintype "passive"))
    )
    (net (code "147") (name "unconnected-(U$4-4-Pad1)") (class "Default")
      (node (ref "U$4") (pin "1") (pinfunction "4_1") (pintype "passive"))
    )
    (net (code "148") (name "unconnected-(U$4-Pad6)") (class "Default")
      (node (ref "U$4") (pin "6") (pinfunction "6_6") (pintype "passive"))
    )
    (net (code "149") (name "unconnected-(U$5-4-Pad1)") (class "Default")
      (node (ref "U$5") (pin "1") (pinfunction "4_1") (pintype "passive"))
    )
    (net (code "150") (name "unconnected-(U$5-Pad6)") (class "Default")
      (node (ref "U$5") (pin "6") (pinfunction "6_6") (pintype "passive"))
    )
    (net (code "151") (name "unconnected-(U$6-4-Pad1)") (class "Default")
      (node (ref "U$6") (pin "1") (pinfunction "4_1") (pintype "passive"))
    )
    (net (code "152") (name "unconnected-(U$6-Pad6)") (class "Default")
      (node (ref "U$6") (pin "6") (pinfunction "6_6") (pintype "passive"))
    )
    (net (code "153") (name "unconnected-(U$7-4-Pad1)") (class "Default")
      (node (ref "U$7") (pin "1") (pinfunction "4_1") (pintype "passive"))
    )
    (net (code "154") (name "unconnected-(U$7-Pad6)") (class "Default")
      (node (ref "U$7") (pin "6") (pinfunction "6_6") (pintype "passive"))
    )
    (net (code "155") (name "unconnected-(U$8-4-Pad1)") (class "Default")
      (node (ref "U$8") (pin "1") (pinfunction "4_1") (pintype "passive"))
    )
    (net (code "156") (name "unconnected-(U$8-Pad6)") (class "Default")
      (node (ref "U$8") (pin "6") (pinfunction "6_6") (pintype "passive"))
    )
    (net (code "157") (name "unconnected-(U$9-4-Pad1)") (class "Default")
      (node (ref "U$9") (pin "1") (pinfunction "4_1") (pintype "passive"))
    )
    (net (code "158") (name "unconnected-(U$9-Pad6)") (class "Default")
      (node (ref "U$9") (pin "6") (pinfunction "6_6") (pintype "passive"))
    )
    (net (code "159") (name "unconnected-(U$10-4-Pad1)") (class "Default")
      (node (ref "U$10") (pin "1") (pinfunction "4_1") (pintype "passive"))
    )
    (net (code "160") (name "unconnected-(U$10-Pad6)") (class "Default")
      (node (ref "U$10") (pin "6") (pinfunction "6_6") (pintype "passive"))
    )
    (net (code "161") (name "unconnected-(U$11-4-Pad1)") (class "Default")
      (node (ref "U$11") (pin "1") (pinfunction "4_1") (pintype "passive"))
    )
    (net (code "162") (name "unconnected-(U$11-Pad6)") (class "Default")
      (node (ref "U$11") (pin "6") (pinfunction "6_6") (pintype "passive"))
    )
    (net (code "163") (name "unconnected-(U$12-4-Pad1)") (class "Default")
      (node (ref "U$12") (pin "1") (pinfunction "4_1") (pintype "passive"))
    )
    (net (code "164") (name "unconnected-(U$12-Pad6)") (class "Default")
      (node (ref "U$12") (pin "6") (pinfunction "6_6") (pintype "passive"))
    )
    (net (code "165") (name "unconnected-(U$13-4-Pad1)") (class "Default")
      (node (ref "U$13") (pin "1") (pinfunction "4_1") (pintype "passive"))
    )
    (net (code "166") (name "unconnected-(U$13-Pad6)") (class "Default")
      (node (ref "U$13") (pin "6") (pinfunction "6_6") (pintype "passive"))
    )
    (net (code "167") (name "unconnected-(U$14-4-Pad1)") (class "Default")
      (node (ref "U$14") (pin "1") (pinfunction "4_1") (pintype "passive"))
    )
    (net (code "168") (name "unconnected-(U$14-Pad6)") (class "Default")
      (node (ref "U$14") (pin "6") (pinfunction "6_6") (pintype "passive"))
    )
    (net (code "169") (name "unconnected-(U$15-4-Pad1)") (class "Default")
      (node (ref "U$15") (pin "1") (pinfunction "4_1") (pintype "passive"))
    )
    (net (code "170") (name "unconnected-(U$15-Pad6)") (class "Default")
      (node (ref "U$15") (pin "6") (pinfunction "6_6") (pintype "passive"))
    )
    (net (code "171") (name "unconnected-(U$16-4-Pad1)") (class "Default")
      (node (ref "U$16") (pin "1") (pinfunction "4_1") (pintype "passive"))
    )
    (net (code "172") (name "unconnected-(U$16-Pad6)") (class "Default")
      (node (ref "U$16") (pin "6") (pinfunction "6_6") (pintype "passive"))
    )
    (net (code "173") (name "unconnected-(U$17-4-Pad1)") (class "Default")
      (node (ref "U$17") (pin "1") (pinfunction "4_1") (pintype "passive"))
    )
    (net (code "174") (name "unconnected-(U$17-Pad6)") (class "Default")
      (node (ref "U$17") (pin "6") (pinfunction "6_6") (pintype "passive"))
    )
    (net (code "175") (name "unconnected-(U$18-4-Pad1)") (class "Default")
      (node (ref "U$18") (pin "1") (pinfunction "4_1") (pintype "passive"))
    )
    (net (code "176") (name "unconnected-(U$18-Pad6)") (class "Default")
      (node (ref "U$18") (pin "6") (pinfunction "6_6") (pintype "passive"))
    )
    (net (code "177") (name "unconnected-(U$19-4-Pad1)") (class "Default")
      (node (ref "U$19") (pin "1") (pinfunction "4_1") (pintype "passive"))
    )
    (net (code "178") (name "unconnected-(U$19-Pad6)") (class "Default")
      (node (ref "U$19") (pin "6") (pinfunction "6_6") (pintype "passive"))
    )
    (net (code "179") (name "unconnected-(U$20-4-Pad1)") (class "Default")
      (node (ref "U$20") (pin "1") (pinfunction "4_1") (pintype "passive"))
    )
    (net (code "180") (name "unconnected-(U$20-Pad6)") (class "Default")
      (node (ref "U$20") (pin "6") (pinfunction "6_6") (pintype "passive"))
    )
    (net (code "181") (name "unconnected-(U$21-4-Pad1)") (class "Default")
      (node (ref "U$21") (pin "1") (pinfunction "4_1") (pintype "passive"))
    )
    (net (code "182") (name "unconnected-(U$21-Pad6)") (class "Default")
      (node (ref "U$21") (pin "6") (pinfunction "6_6") (pintype "passive"))
    )
    (net (code "183") (name "unconnected-(U$22-4-Pad1)") (class "Default")
      (node (ref "U$22") (pin "1") (pinfunction "4_1") (pintype "passive"))
    )
    (net (code "184") (name "unconnected-(U$22-Pad6)") (class "Default")
      (node (ref "U$22") (pin "6") (pinfunction "6_6") (pintype "passive"))
    )
    (net (code "185") (name "unconnected-(U$23-4-Pad1)") (class "Default")
      (node (ref "U$23") (pin "1") (pinfunction "4_1") (pintype "passive"))
    )
    (net (code "186") (name "unconnected-(U$23-Pad6)") (class "Default")
      (node (ref "U$23") (pin "6") (pinfunction "6_6") (pintype "passive"))
    )
    (net (code "187") (name "unconnected-(U$24-4-Pad1)") (class "Default")
      (node (ref "U$24") (pin "1") (pinfunction "4_1") (pintype "passive"))
    )
    (net (code "188") (name "unconnected-(U$24-Pad6)") (class "Default")
      (node (ref "U$24") (pin "6") (pinfunction "6_6") (pintype "passive"))
    )
    (net (code "189") (name "unconnected-(U$25-4-Pad1)") (class "Default")
      (node (ref "U$25") (pin "1") (pinfunction "4_1") (pintype "passive"))
    )
    (net (code "190") (name "unconnected-(U$25-Pad6)") (class "Default")
      (node (ref "U$25") (pin "6") (pinfunction "6_6") (pintype "passive"))
    )
    (net (code "191") (name "unconnected-(U$26-4-Pad1)") (class "Default")
      (node (ref "U$26") (pin "1") (pinfunction "4_1") (pintype "passive"))
    )
    (net (code "192") (name "unconnected-(U$26-Pad6)") (class "Default")
      (node (ref "U$26") (pin "6") (pinfunction "6_6") (pintype "passive"))
    )
    (net (code "193") (name "unconnected-(U$27-4-Pad1)") (class "Default")
      (node (ref "U$27") (pin "1") (pinfunction "4_1") (pintype "passive"))
    )
    (net (code "194") (name "unconnected-(U$27-Pad6)") (class "Default")
      (node (ref "U$27") (pin "6") (pinfunction "6_6") (pintype "passive"))
    )
    (net (code "195") (name "unconnected-(U$28-4-Pad1)") (class "Default")
      (node (ref "U$28") (pin "1") (pinfunction "4_1") (pintype "passive"))
    )
    (net (code "196") (name "unconnected-(U$28-Pad6)") (class "Default")
      (node (ref "U$28") (pin "6") (pinfunction "6_6") (pintype "passive"))
    )
    (net (code "197") (name "unconnected-(U$29-4-Pad1)") (class "Default")
      (node (ref "U$29") (pin "1") (pinfunction "4_1") (pintype "passive"))
    )
    (net (code "198") (name "unconnected-(U$29-Pad6)") (class "Default")
      (node (ref "U$29") (pin "6") (pinfunction "6_6") (pintype "passive"))
    )
    (net (code "199") (name "unconnected-(U$30-4-Pad1)") (class "Default")
      (node (ref "U$30") (pin "1") (pinfunction "4_1") (pintype "passive"))
    )
    (net (code "200") (name "unconnected-(U$30-Pad6)") (class "Default")
      (node (ref "U$30") (pin "6") (pinfunction "6_6") (pintype "passive"))
    )
    (net (code "201") (name "unconnected-(U$34-10-PadP$10)") (class "Default")
      (node (ref "U$34") (pin "P$10") (pinfunction "10_P$10") (pintype "passive"))
    )
    (net (code "202") (name "unconnected-(U$35-6-PadP$6)") (class "Default")
      (node (ref "U$35") (pin "P$6") (pinfunction "6_P$6") (pintype "passive"))
    )
    (net (code "203") (name "unconnected-(U$35-7-PadP$7)") (class "Default")
      (node (ref "U$35") (pin "P$7") (pinfunction "7_P$7") (pintype "passive"))
    )
    (net (code "204") (name "unconnected-(U$35-8-PadP$8)") (class "Default")
      (node (ref "U$35") (pin "P$8") (pinfunction "8_P$8") (pintype "passive"))
    )
    (net (code "205") (name "unconnected-(U$35-9-PadP$9)") (class "Default")
      (node (ref "U$35") (pin "P$9") (pinfunction "9_P$9") (pintype "passive"))
    )
    (net (code "206") (name "unconnected-(U$35-10-PadP$10)") (class "Default")
      (node (ref "U$35") (pin "P$10") (pinfunction "10_P$10") (pintype "passive"))
    )
    (net (code "207") (name "unconnected-(U$36-10-PadP$10)") (class "Default")
      (node (ref "U$36") (pin "P$10") (pinfunction "10_P$10") (pintype "passive"))
    )
    (net (code "208") (name "unconnected-(U$37-2-PadP$2)") (class "Default")
      (node (ref "U$37") (pin "P$2") (pinfunction "2_P$2") (pintype "passive"))
    )
    (net (code "209") (name "unconnected-(U$37-3-PadP$3)") (class "Default")
      (node (ref "U$37") (pin "P$3") (pinfunction "3_P$3") (pintype "passive"))
    )
    (net (code "210") (name "unconnected-(U$37-4-PadP$4)") (class "Default")
      (node (ref "U$37") (pin "P$4") (pinfunction "4_P$4") (pintype "passive"))
    )
    (net (code "211") (name "unconnected-(U$37-5-PadP$5)") (class "Default")
      (node (ref "U$37") (pin "P$5") (pinfunction "5_P$5") (pintype "passive"))
    )
    (net (code "212") (name "unconnected-(U$37-10-PadP$10)") (class "Default")
      (node (ref "U$37") (pin "P$10") (pinfunction "10_P$10") (pintype "passive"))
    )
    (net (code "213") (name "unconnected-(U$59-4-Pad1)") (class "Default")
      (node (ref "U$59") (pin "1") (pinfunction "4_1") (pintype "passive"))
    )
    (net (code "214") (name "unconnected-(U$59-Pad6)") (class "Default")
      (node (ref "U$59") (pin "6") (pinfunction "6_6") (pintype "passive"))
    )
    (net (code "215") (name "unconnected-(U$60-Pad1)") (class "Default")
      (node (ref "U$60") (pin "1") (pinfunction "1_1") (pintype "passive"))
    )
    (net (code "216") (name "unconnected-(U$61-Pad1)") (class "Default")
      (node (ref "U$61") (pin "1") (pinfunction "1_1") (pintype "passive"))
    )
    (net (code "217") (name "unconnected-(U1-SER-Pad10)") (class "Default")
      (node (ref "U1") (pin "10") (pinfunction "SER_10") (pintype "input"))
    )
    (net (code "218") (name "unconnected-(U1-~{QH}-Pad7)") (class "Default")
      (node (ref "U1") (pin "7") (pinfunction "~{QH}_7") (pintype "input"))
    )
    (net (code "219") (name "unconnected-(U2-~{QH}-Pad7)") (class "Default")
      (node (ref "U2") (pin "7") (pinfunction "~{QH}_7") (pintype "input"))
    )
    (net (code "220") (name "unconnected-(U3-~{QH}-Pad7)") (class "Default")
      (node (ref "U3") (pin "7") (pinfunction "~{QH}_7") (pintype "input"))
    )
    (net (code "221") (name "unconnected-(U4-SER-Pad10)") (class "Default")
      (node (ref "U4") (pin "10") (pinfunction "SER_10") (pintype "input"))
    )
    (net (code "222") (name "unconnected-(U4-~{QH}-Pad7)") (class "Default")
      (node (ref "U4") (pin "7") (pinfunction "~{QH}_7") (pintype "input"))
    )
    (net (code "223") (name "unconnected-(U5-~{QH}-Pad7)") (class "Default")
      (node (ref "U5") (pin "7") (pinfunction "~{QH}_7") (pintype "input"))
    )
    (net (code "224") (name "unconnected-(U6-~{QH}-Pad7)") (class "Default")
      (node (ref "U6") (pin "7") (pinfunction "~{QH}_7") (pintype "input"))
    )
  )
)
